# BlueBus.net
KiCad netlist of a schematic drawn in EAGLE
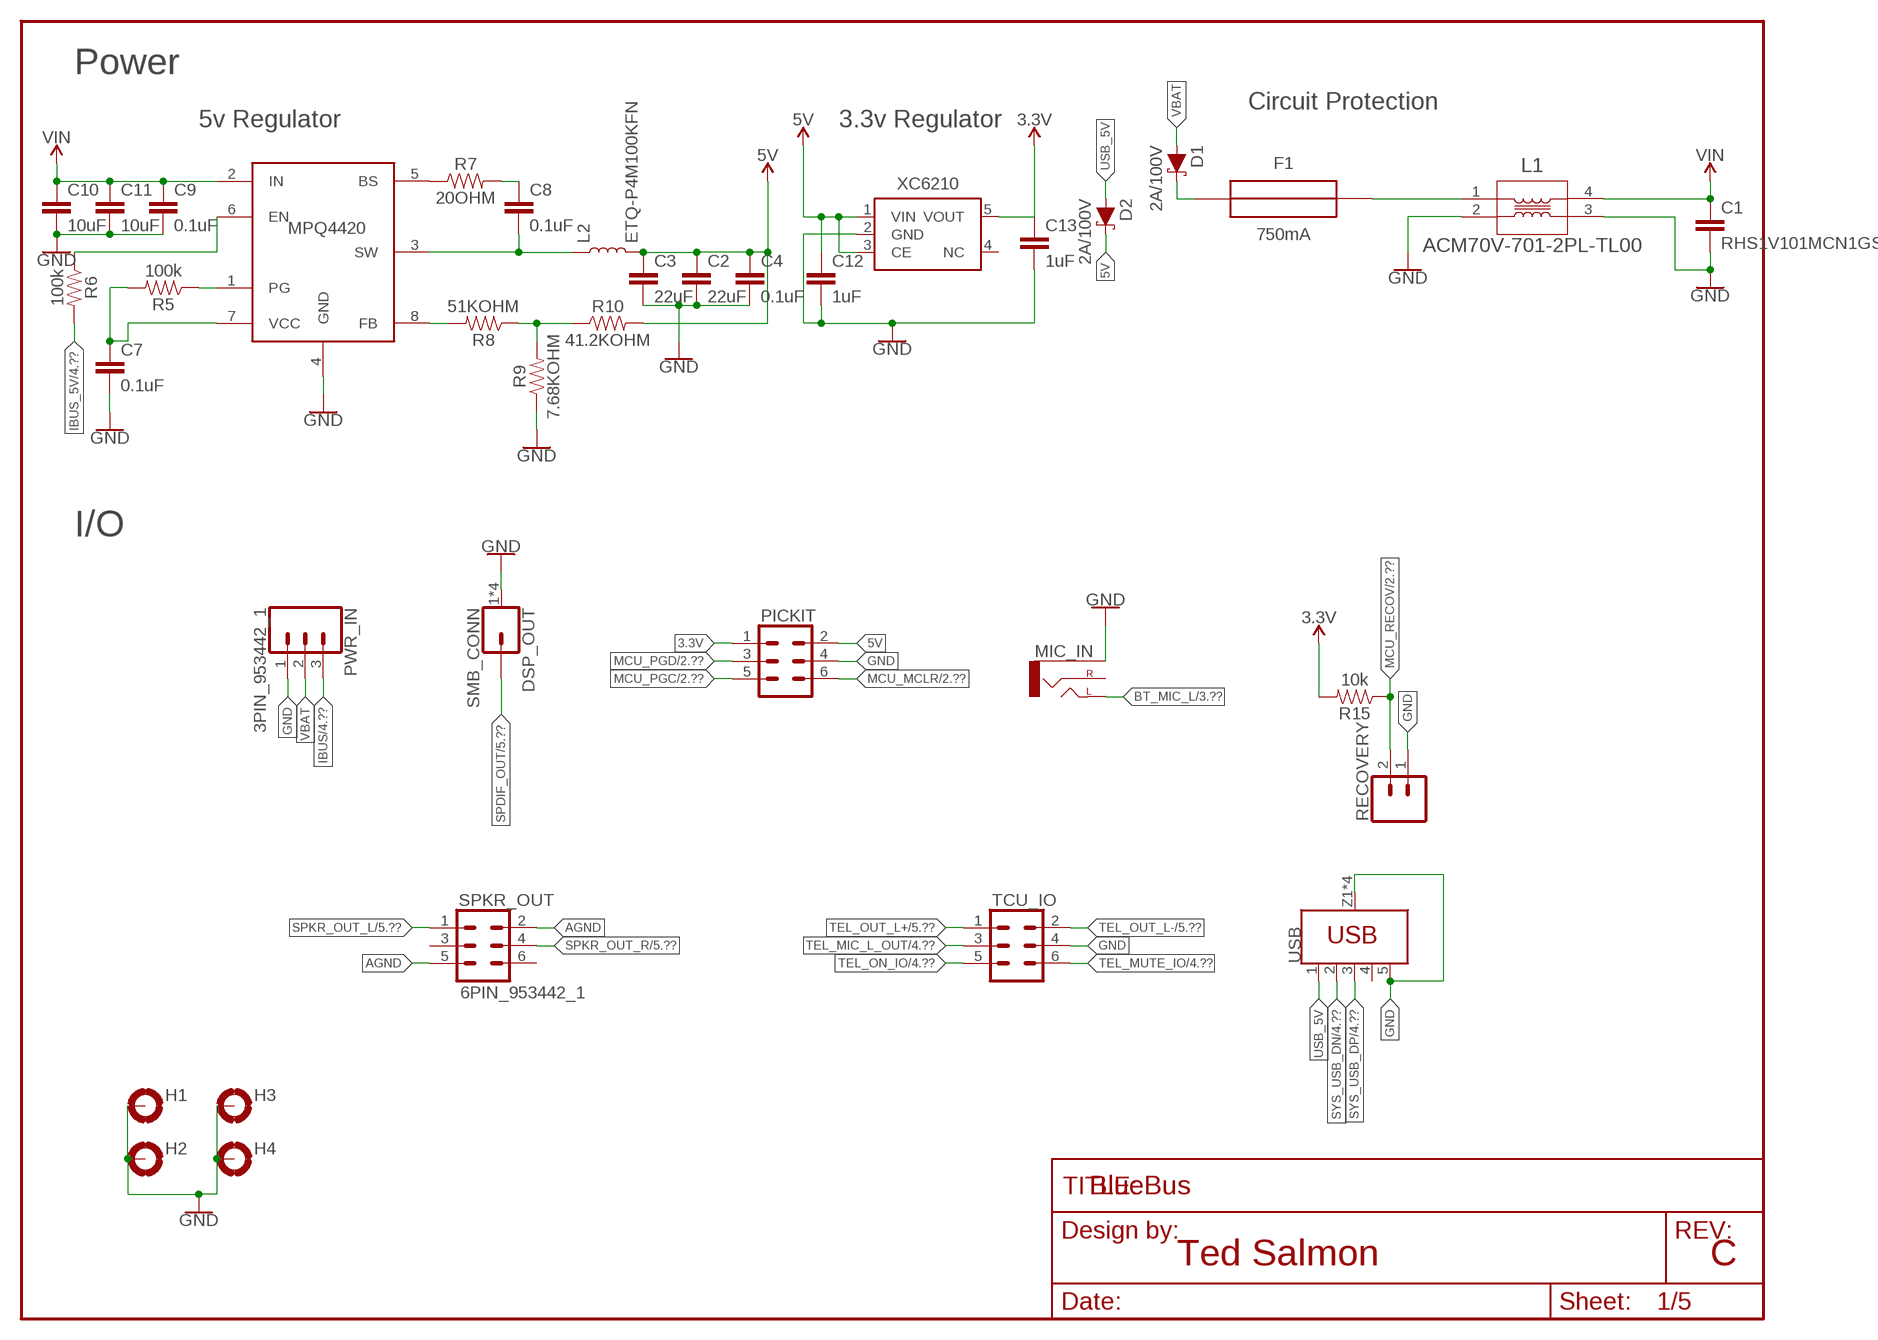
[diagram p0: schematic, sheet 1]
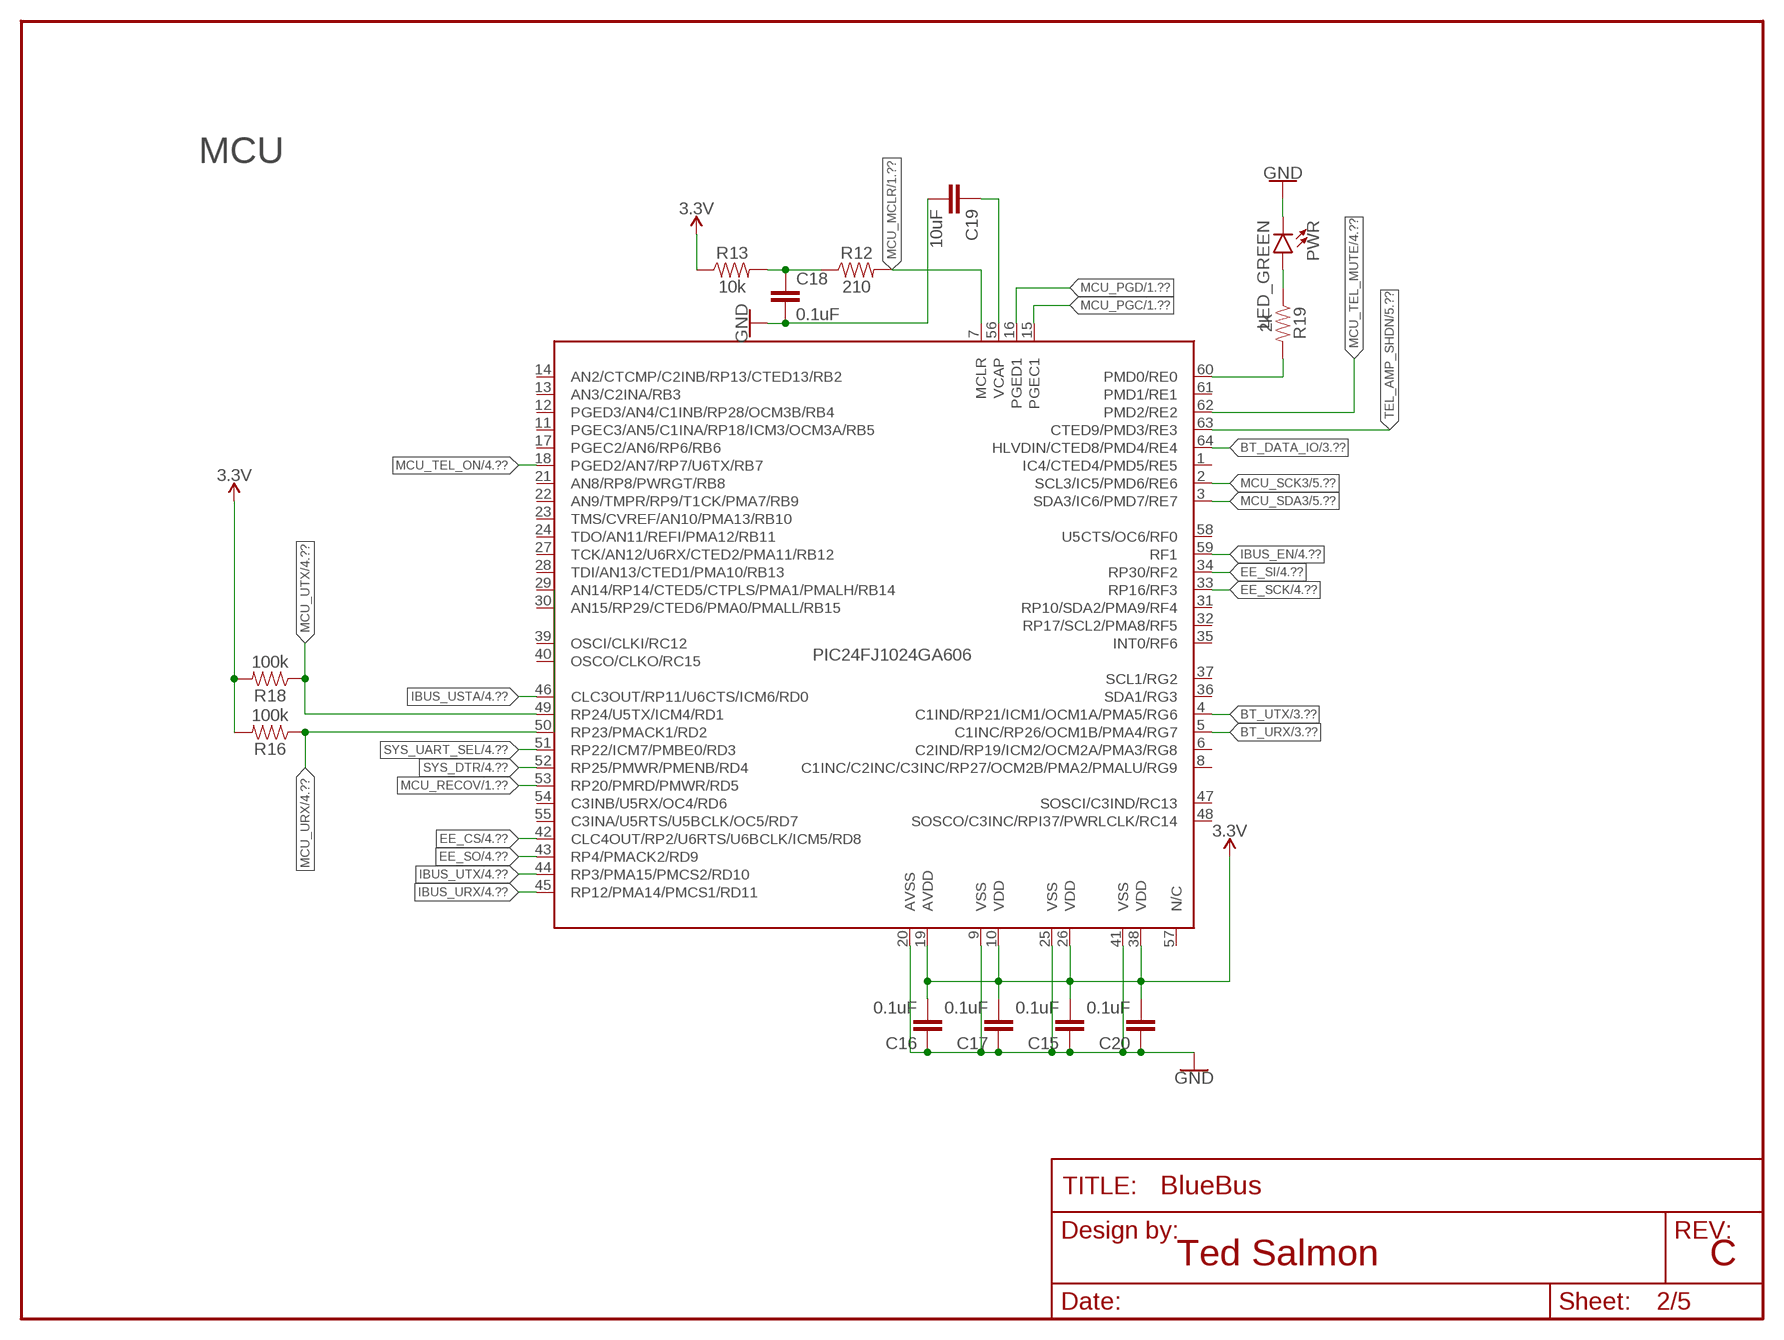
[diagram p1: schematic, sheet 2]
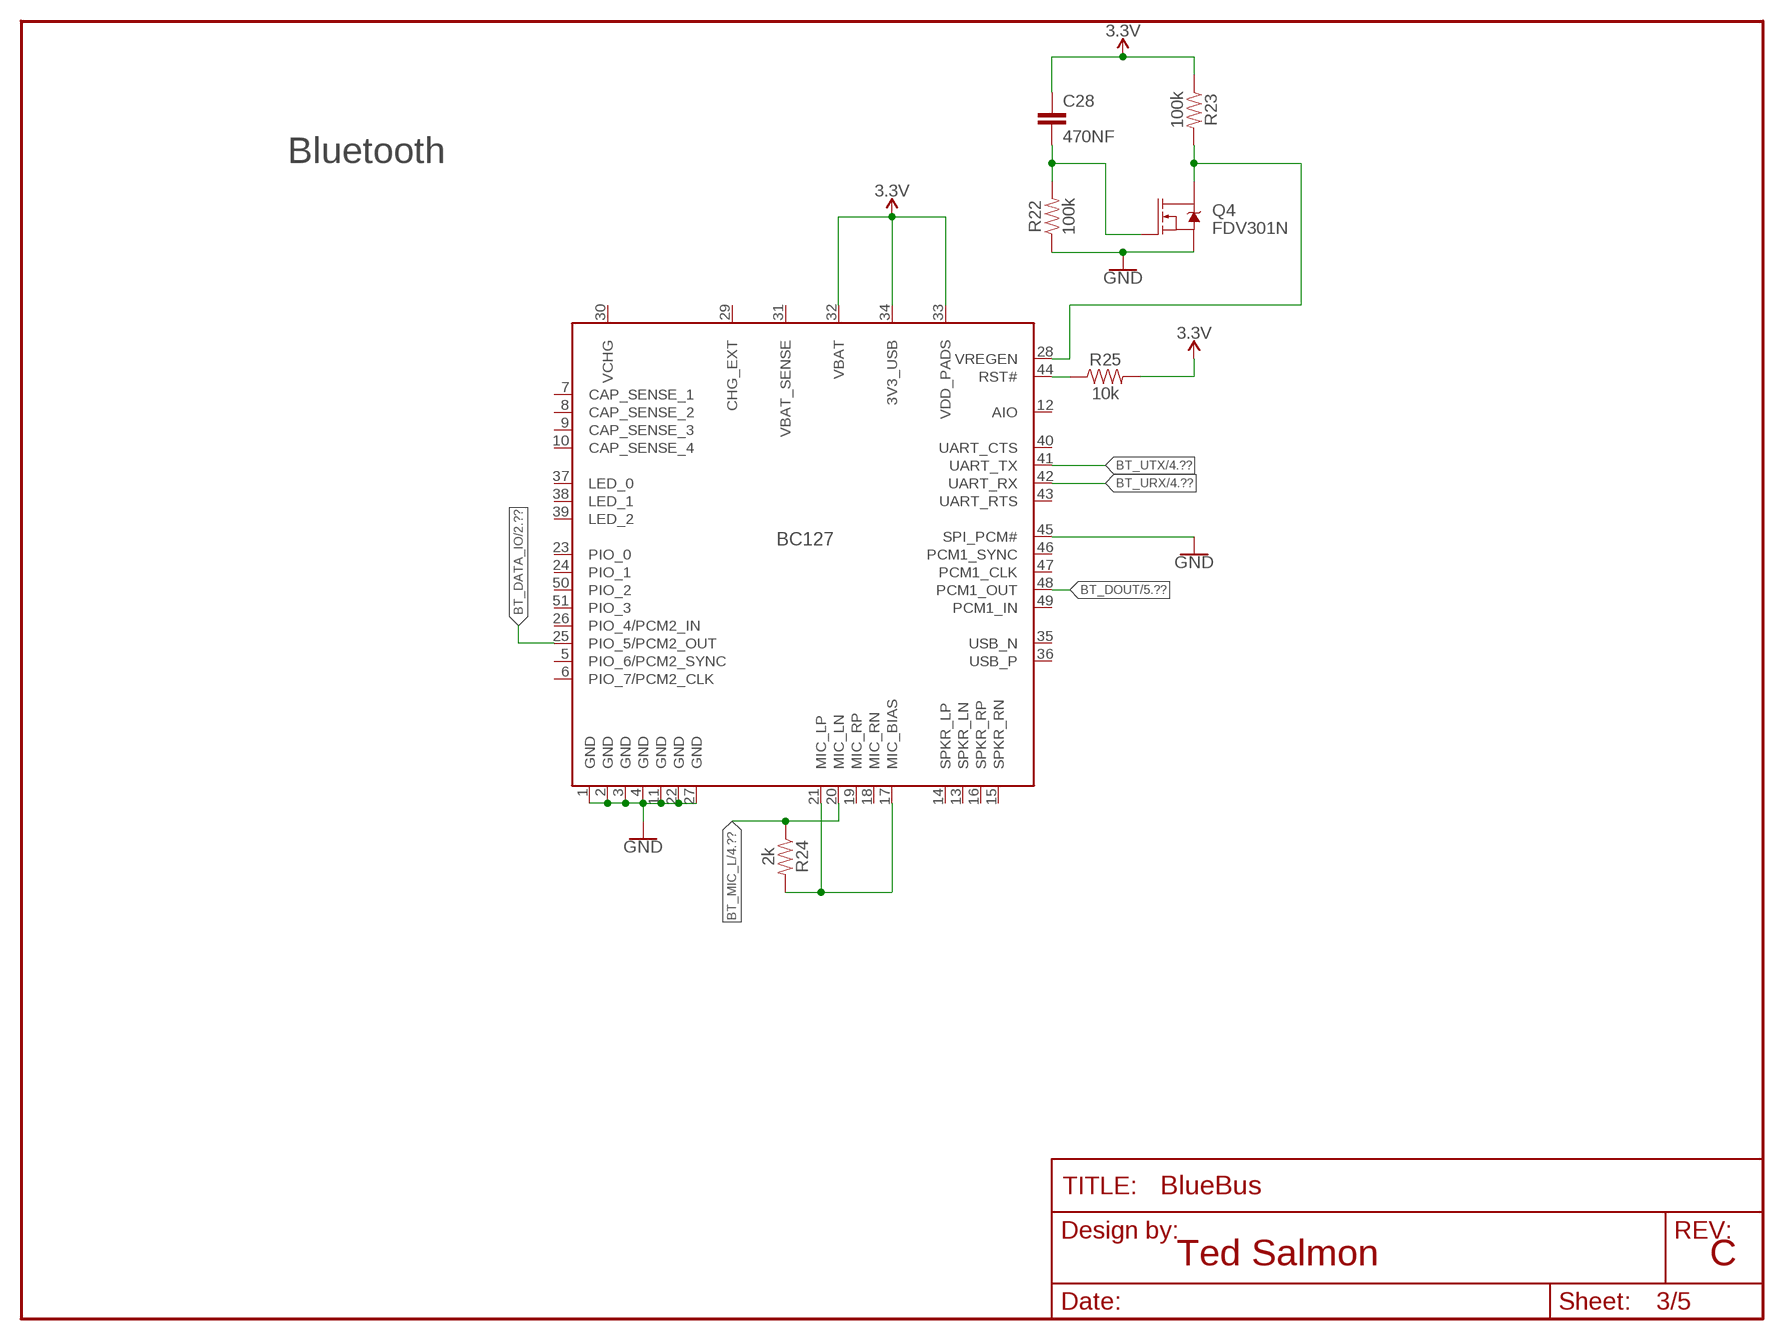
[diagram p2: schematic, sheet 3]
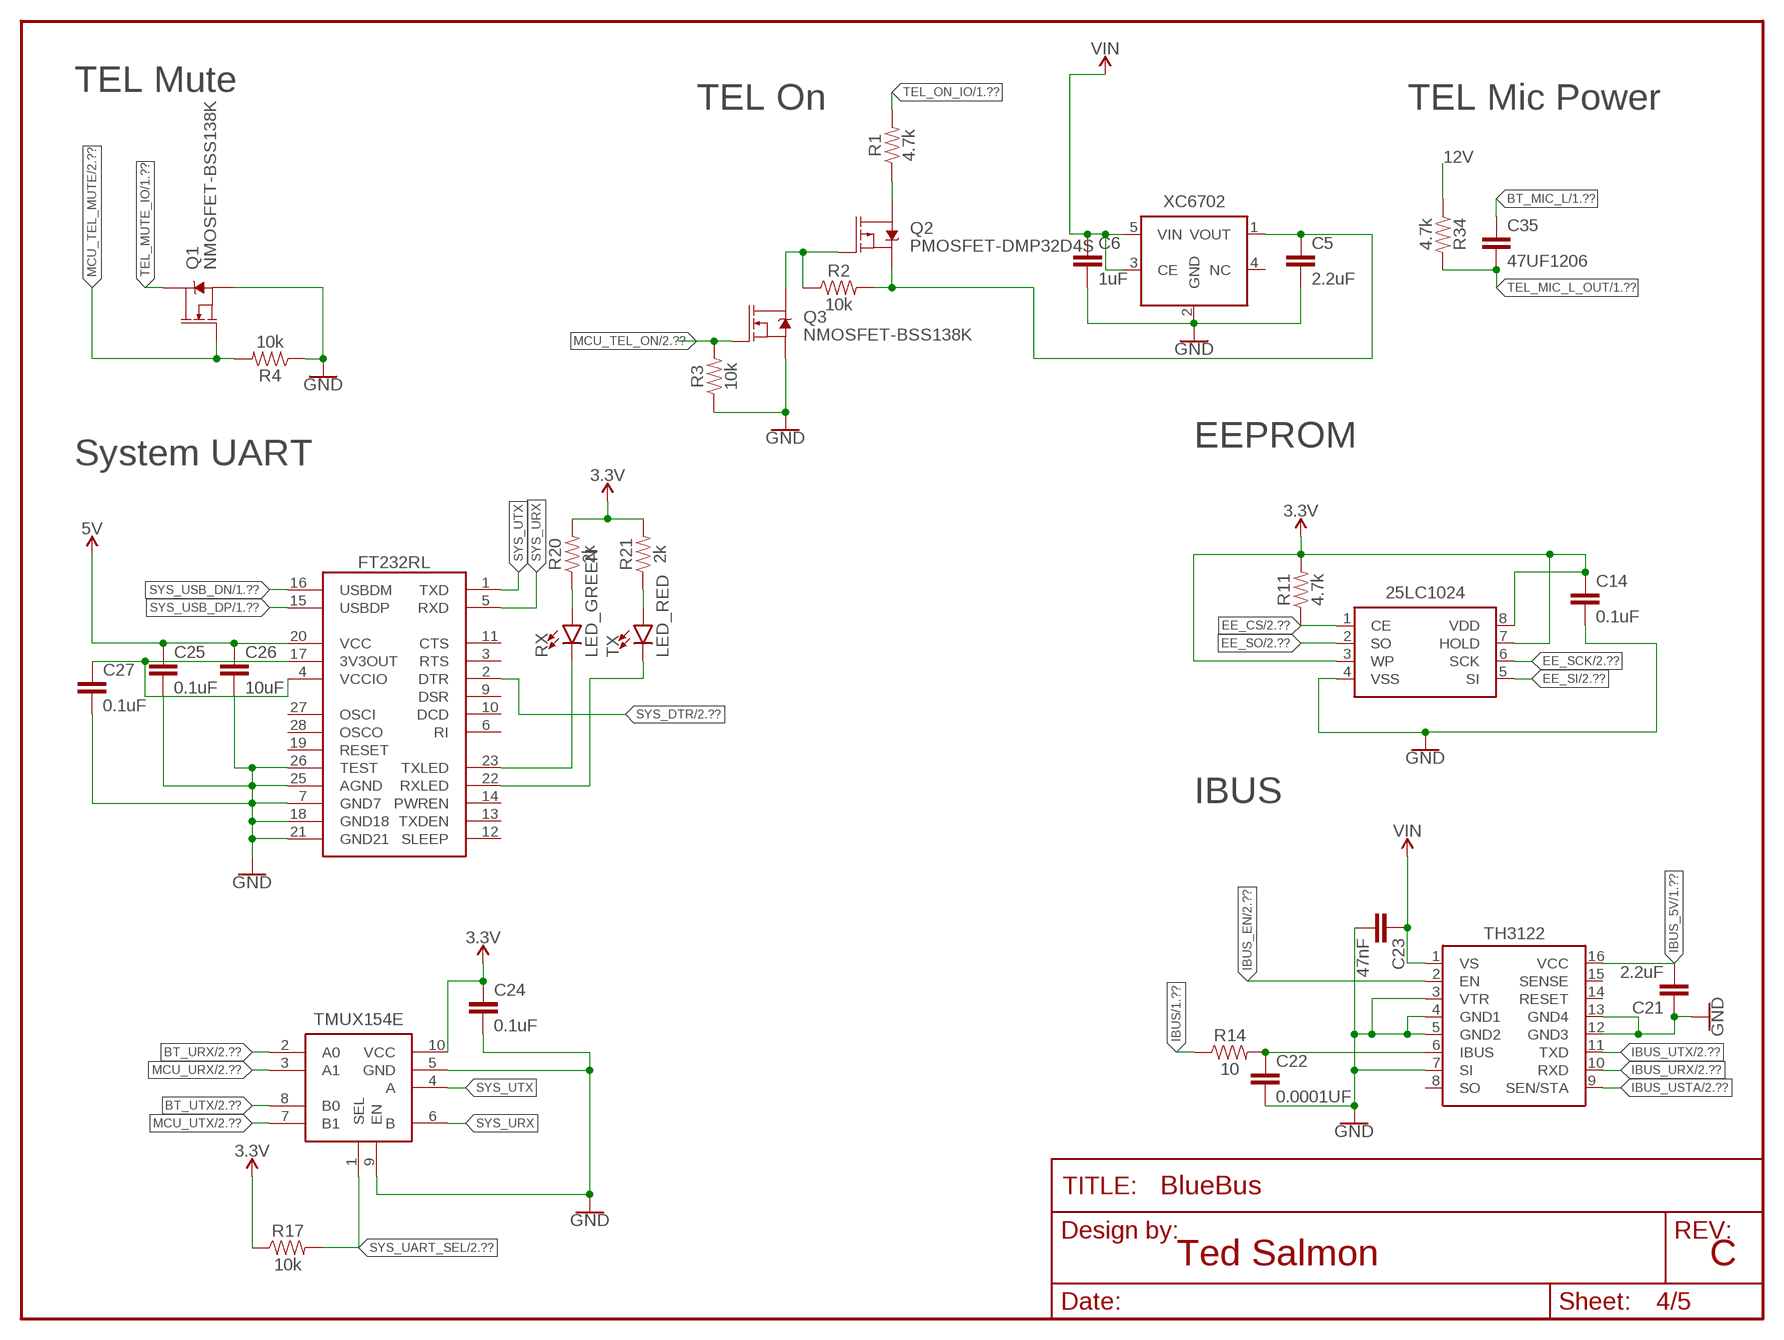
[diagram p3: schematic, sheet 4]
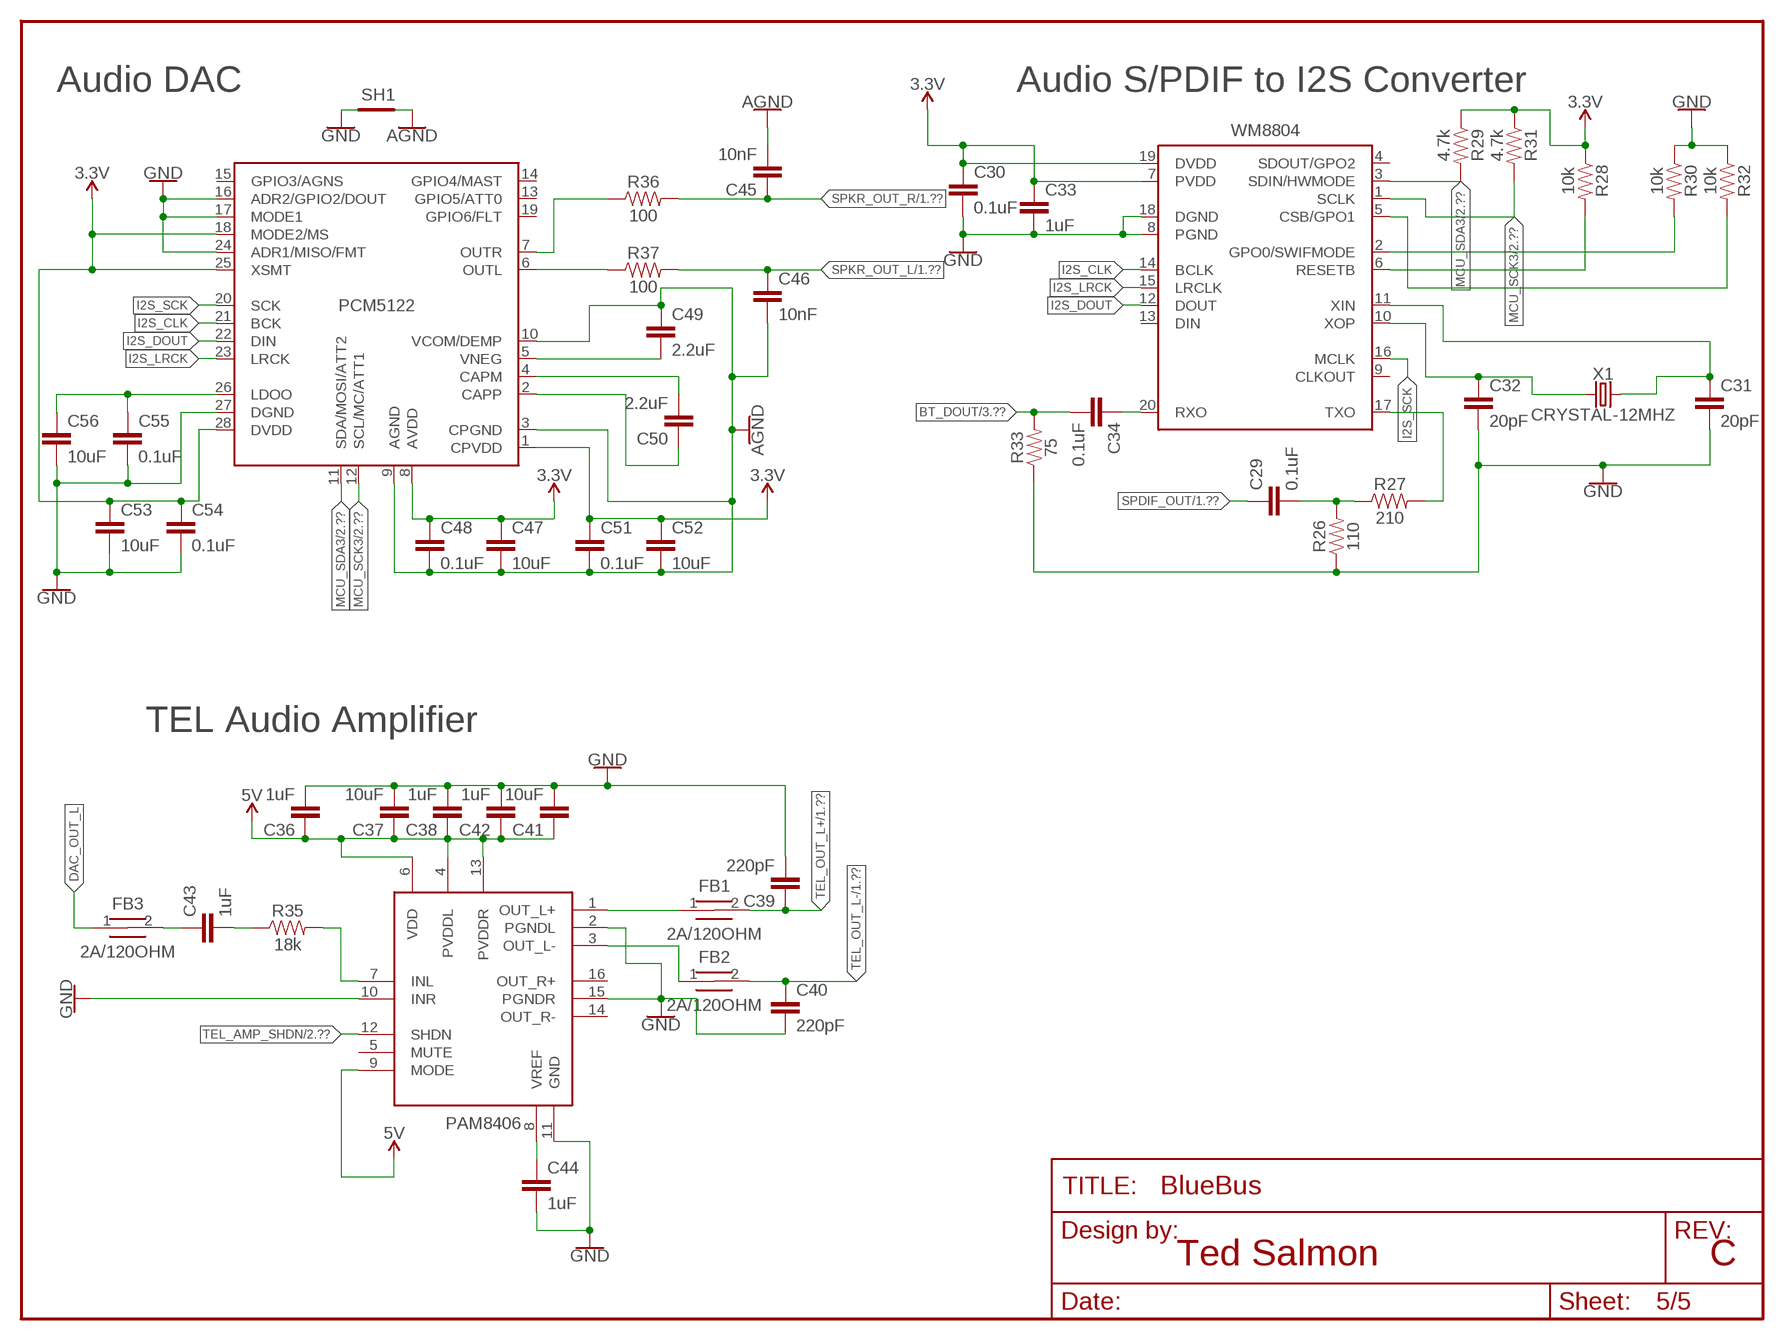
[diagram p4: schematic, sheet 5]

(export (version "E")
  (design (tool "Eeschema 10.0.6"))
  (components
    (comp (ref "C1")
      (value "RHS1V101MCN1GS")
      (footprint "eagle-import:RHS1V101MCN1GS")
      (fields (field (name "MFG") "Nichicon"))
      (libsource (lib "eagle-import") (part "RHS1V101MCN1GS"))
    )
    (comp (ref "C2")
      (value "22uF")
      (footprint "eagle-import:0805")
      (fields (field (name "MFG") "TDK"))
      (libsource (lib "eagle-import") (part "22UF"))
    )
    (comp (ref "C3")
      (value "22uF")
      (footprint "eagle-import:0805")
      (fields (field (name "MFG") "TDK"))
      (libsource (lib "eagle-import") (part "22UF"))
    )
    (comp (ref "C4")
      (value "0.1uF")
      (footprint "eagle-import:0805")
      (fields (field (name "MFG") "KEMET"))
      (libsource (lib "eagle-import") (part "0.1UF"))
    )
    (comp (ref "C7")
      (value "0.1uF")
      (footprint "eagle-import:0805")
      (fields (field (name "MFG") "KEMET"))
      (libsource (lib "eagle-import") (part "0.1UF"))
    )
    (comp (ref "C8")
      (value "0.1uF")
      (footprint "eagle-import:0805")
      (fields (field (name "MFG") "KEMET"))
      (libsource (lib "eagle-import") (part "0.1UF"))
    )
    (comp (ref "C9")
      (value "0.1uF")
      (footprint "eagle-import:0805")
      (fields (field (name "MFG") "KEMET"))
      (libsource (lib "eagle-import") (part "0.1UF"))
    )
    (comp (ref "C10")
      (value "10uF")
      (footprint "eagle-import:1206")
      (fields (field (name "MFG") "TDK"))
      (libsource (lib "eagle-import") (part "10UF"))
    )
    (comp (ref "C11")
      (value "10uF")
      (footprint "eagle-import:1206")
      (fields (field (name "MFG") "TDK"))
      (libsource (lib "eagle-import") (part "10UF"))
    )
    (comp (ref "C12")
      (value "1uF")
      (footprint "eagle-import:0805")
      (fields (field (name "MFG") "TDK"))
      (libsource (lib "eagle-import") (part "1UF"))
    )
    (comp (ref "C13")
      (value "1uF")
      (footprint "eagle-import:0805")
      (fields (field (name "MFG") "TDK"))
      (libsource (lib "eagle-import") (part "1UF"))
    )
    (comp (ref "D1")
      (value "2A/100V")
      (footprint "eagle-import:SOD123")
      (fields (field (name "MFG") "STMicroelectronics"))
      (libsource (lib "eagle-import") (part "SCHOTTKYDIODE2A100V"))
    )
    (comp (ref "D2")
      (value "2A/100V")
      (footprint "eagle-import:SOD123")
      (fields (field (name "MFG") "STMicroelectronics"))
      (libsource (lib "eagle-import") (part "SCHOTTKYDIODE2A100V"))
    )
    (comp (ref "DSP_OUT")
      (value "SMB_CONN")
      (footprint "eagle-import:MOLEX_SMB")
      (libsource (lib "eagle-import") (part "SMB_CONN"))
    )
    (comp (ref "F1")
      (value "750mA")
      (footprint "eagle-import:LITTLEFUSE")
      (fields (field (name "MFG") "LITTLEBLOCK"))
      (libsource (lib "eagle-import") (part "LITTLEBLOCK_FUSE_.75A"))
    )
    (comp (ref "FRAME1")
      (value "FRAME-LETTER")
      (footprint "eagle-import:DUMMY")
      (libsource (lib "eagle-import") (part "FRAME-LETTER"))
    )
    (comp (ref "H1")
      (value "2,0-PAD")
      (footprint "eagle-import:2.0-PAD")
      (libsource (lib "eagle-import") (part "2,0-PAD"))
    )
    (comp (ref "H2")
      (value "2,0-PAD")
      (footprint "eagle-import:2.0-PAD")
      (libsource (lib "eagle-import") (part "2,0-PAD"))
    )
    (comp (ref "H3")
      (value "2,0-PAD")
      (footprint "eagle-import:2.0-PAD")
      (libsource (lib "eagle-import") (part "2,0-PAD"))
    )
    (comp (ref "H4")
      (value "2,0-PAD")
      (footprint "eagle-import:2.0-PAD")
      (libsource (lib "eagle-import") (part "2,0-PAD"))
    )
    (comp (ref "L1")
      (value "ACM70V-701-2PL-TL00")
      (footprint "eagle-import:ACM70V-701-2PL-TL00")
      (fields (field (name "MFG") "TDK"))
      (libsource (lib "eagle-import") (part "ACM70V-701-2PL-TL00"))
    )
    (comp (ref "L2")
      (value "ETQ-P4M100KFN")
      (footprint "eagle-import:PCC-M0648M-LE")
      (fields (field (name "MFG") "PANASONIC"))
      (libsource (lib "eagle-import") (part "ETQ-P4M100KFN"))
    )
    (comp (ref "MIC_IN")
      (value "AUDIO-CUI-SJ-3523-SMT")
      (footprint "eagle-import:AUDIO-CUI-SJ-352X-SMT")
      (libsource (lib "eagle-import") (part "AUDIO-CUI-SJ-3523-SMT"))
    )
    (comp (ref "MPQ4420")
      (value "MPQ4420")
      (footprint "eagle-import:TSOT23-8")
      (libsource (lib "eagle-import") (part "MPQ4420"))
    )
    (comp (ref "PICKIT")
      (value "6PIN_JUMPER")
      (footprint "eagle-import:2X3")
      (libsource (lib "eagle-import") (part "6PIN_JUMPER"))
    )
    (comp (ref "PWR_IN")
      (value "3PIN_953442_1")
      (footprint "eagle-import:TE_MQS_3PIN")
      (libsource (lib "eagle-import") (part "3PIN_953442_1"))
    )
    (comp (ref "R5")
      (value "100k")
      (footprint "eagle-import:0805")
      (libsource (lib "eagle-import") (part "100KOHM"))
    )
    (comp (ref "R6")
      (value "100k")
      (footprint "eagle-import:0805")
      (libsource (lib "eagle-import") (part "100KOHM"))
    )
    (comp (ref "R7")
      (value "20OHM")
      (footprint "eagle-import:0805")
      (libsource (lib "eagle-import") (part "20OHM"))
    )
    (comp (ref "R8")
      (value "51KOHM")
      (footprint "eagle-import:0805")
      (libsource (lib "eagle-import") (part "51KOHM"))
    )
    (comp (ref "R9")
      (value "7.68KOHM")
      (footprint "eagle-import:0805")
      (libsource (lib "eagle-import") (part "7.68KOHM"))
    )
    (comp (ref "R10")
      (value "41.2KOHM")
      (footprint "eagle-import:0805")
      (libsource (lib "eagle-import") (part "41.2KOHM"))
    )
    (comp (ref "R15")
      (value "10k")
      (footprint "eagle-import:0805")
      (fields (field (name "MFG") "Panasonic"))
      (libsource (lib "eagle-import") (part "10KOHM"))
    )
    (comp (ref "RECOVERY")
      (value "2PIN_JUMPER")
      (footprint "eagle-import:1X02")
      (libsource (lib "eagle-import") (part "2PIN_JUMPER"))
    )
    (comp (ref "SPKR_OUT")
      (value "6PIN_953442_1")
      (footprint "eagle-import:TE_MQS_6PIN")
      (libsource (lib "eagle-import") (part "6PIN_953442_1"))
    )
    (comp (ref "TCU_IO")
      (value "6PIN_5_103166_1")
      (footprint "eagle-import:TE_AMPMODU_6_PIN")
      (libsource (lib "eagle-import") (part "6PIN_5_103166_1"))
    )
    (comp (ref "USB")
      (value "USB_WURTH_629105150521")
      (footprint "eagle-import:629105150521")
      (libsource (lib "eagle-import") (part "USB_WURTH_629105150521"))
    )
    (comp (ref "XC6210")
      (value "XC6210SOT25")
      (footprint "eagle-import:SOT23-5")
      (libsource (lib "eagle-import") (part "XC6210SOT25"))
    )
    (comp (ref "25LC1024")
      (value "25LC1024")
      (footprint "eagle-import:SOIJ-8")
      (libsource (lib "eagle-import") (part "25LC1024"))
    )
    (comp (ref "C5")
      (value "2.2uF")
      (footprint "eagle-import:0805")
      (fields (field (name "MFG") "TDK"))
      (libsource (lib "eagle-import") (part "2.2UF"))
    )
    (comp (ref "C6")
      (value "1uF")
      (footprint "eagle-import:0805")
      (fields (field (name "MFG") "TDK"))
      (libsource (lib "eagle-import") (part "1UF"))
    )
    (comp (ref "C14")
      (value "0.1uF")
      (footprint "eagle-import:0805")
      (fields (field (name "MFG") "KEMET"))
      (libsource (lib "eagle-import") (part "0.1UF"))
    )
    (comp (ref "C21")
      (value "2.2uF")
      (footprint "eagle-import:0805")
      (fields (field (name "MFG") "TDK"))
      (libsource (lib "eagle-import") (part "2.2UF"))
    )
    (comp (ref "C22")
      (value "0.0001UF")
      (footprint "eagle-import:0805")
      (libsource (lib "eagle-import") (part "0.0001UF"))
    )
    (comp (ref "C23")
      (value "47nF")
      (footprint "eagle-import:0805")
      (fields (field (name "MFG") "AVX"))
      (libsource (lib "eagle-import") (part "47NF"))
    )
    (comp (ref "C24")
      (value "0.1uF")
      (footprint "eagle-import:0805")
      (fields (field (name "MFG") "KEMET"))
      (libsource (lib "eagle-import") (part "0.1UF"))
    )
    (comp (ref "C25")
      (value "0.1uF")
      (footprint "eagle-import:0805")
      (fields (field (name "MFG") "KEMET"))
      (libsource (lib "eagle-import") (part "0.1UF"))
    )
    (comp (ref "C26")
      (value "10uF")
      (footprint "eagle-import:0805")
      (fields (field (name "MFG") "TDK"))
      (libsource (lib "eagle-import") (part "10UF2012"))
    )
    (comp (ref "C27")
      (value "0.1uF")
      (footprint "eagle-import:0805")
      (fields (field (name "MFG") "KEMET"))
      (libsource (lib "eagle-import") (part "0.1UF"))
    )
    (comp (ref "C35")
      (value "47UF1206")
      (footprint "eagle-import:1206")
      (fields (field (name "MFG") "MURATA"))
      (libsource (lib "eagle-import") (part "47UF1206"))
    )
    (comp (ref "FRAME3")
      (value "FRAME-LETTER")
      (footprint "eagle-import:DUMMY")
      (libsource (lib "eagle-import") (part "FRAME-LETTER"))
    )
    (comp (ref "FT232RL")
      (value "FT232RL")
      (footprint "eagle-import:SSOP28")
      (libsource (lib "eagle-import") (part "FT232RL"))
    )
    (comp (ref "Q1")
      (value "NMOSFET-BSS138K")
      (footprint "eagle-import:SOT-23")
      (libsource (lib "eagle-import") (part "NMOSFET-BSS138K"))
    )
    (comp (ref "Q2")
      (value "PMOSFET-DMP32D4S")
      (footprint "eagle-import:SOT-23")
      (fields (field (name "MFG") "Diodes Inc") (field (name "MPN") "DMP32D4S"))
      (libsource (lib "eagle-import") (part "PMOSFET-DMP32D4S"))
    )
    (comp (ref "Q3")
      (value "NMOSFET-BSS138K")
      (footprint "eagle-import:SOT-23")
      (libsource (lib "eagle-import") (part "NMOSFET-BSS138K"))
    )
    (comp (ref "R1")
      (value "4.7k")
      (footprint "eagle-import:0805")
      (fields (field (name "MFG") "Panasonic"))
      (libsource (lib "eagle-import") (part "4.7KOHM"))
    )
    (comp (ref "R2")
      (value "10k")
      (footprint "eagle-import:0805")
      (fields (field (name "MFG") "Panasonic"))
      (libsource (lib "eagle-import") (part "10KOHM"))
    )
    (comp (ref "R3")
      (value "10k")
      (footprint "eagle-import:0805")
      (fields (field (name "MFG") "Panasonic"))
      (libsource (lib "eagle-import") (part "10KOHM"))
    )
    (comp (ref "R4")
      (value "10k")
      (footprint "eagle-import:0805")
      (fields (field (name "MFG") "Panasonic"))
      (libsource (lib "eagle-import") (part "10KOHM"))
    )
    (comp (ref "R11")
      (value "4.7k")
      (footprint "eagle-import:0805")
      (fields (field (name "MFG") "Panasonic"))
      (libsource (lib "eagle-import") (part "4.7KOHM"))
    )
    (comp (ref "R14")
      (value "10")
      (footprint "eagle-import:0805")
      (fields (field (name "MFG") "Panasonic"))
      (libsource (lib "eagle-import") (part "10OHM"))
    )
    (comp (ref "R17")
      (value "10k")
      (footprint "eagle-import:0805")
      (fields (field (name "MFG") "Panasonic"))
      (libsource (lib "eagle-import") (part "10KOHM"))
    )
    (comp (ref "R20")
      (value "2k")
      (footprint "eagle-import:0805")
      (fields (field (name "MFG") "ROHM"))
      (libsource (lib "eagle-import") (part "2KOHM"))
    )
    (comp (ref "R21")
      (value "2k")
      (footprint "eagle-import:0805")
      (fields (field (name "MFG") "ROHM"))
      (libsource (lib "eagle-import") (part "2KOHM"))
    )
    (comp (ref "R34")
      (value "4.7k")
      (footprint "eagle-import:0805")
      (fields (field (name "MFG") "Panasonic"))
      (libsource (lib "eagle-import") (part "4.7KOHM"))
    )
    (comp (ref "RX")
      (value "LED_GREEN")
      (footprint "eagle-import:LED-0805")
      (libsource (lib "eagle-import") (part "LED_GREEN"))
    )
    (comp (ref "TH3122")
      (value "TH3122.4")
      (footprint "eagle-import:SOIC16DF")
      (libsource (lib "eagle-import") (part "TH3122.4"))
    )
    (comp (ref "TMUX154E")
      (value "TMUX154E")
      (footprint "eagle-import:VSSOP10")
      (libsource (lib "eagle-import") (part "TMUX154E"))
    )
    (comp (ref "TX")
      (value "LED_RED")
      (footprint "eagle-import:LED-0805")
      (libsource (lib "eagle-import") (part "LED_RED"))
    )
    (comp (ref "XC6702")
      (value "XC6702DC018PR-G")
      (footprint "eagle-import:SOT-89-5")
      (libsource (lib "eagle-import") (part "XC6702DC018PR-G"))
    )
    (comp (ref "C15")
      (value "0.1uF")
      (footprint "eagle-import:0805")
      (fields (field (name "MFG") "KEMET"))
      (libsource (lib "eagle-import") (part "0.1UF"))
    )
    (comp (ref "C16")
      (value "0.1uF")
      (footprint "eagle-import:0805")
      (fields (field (name "MFG") "KEMET"))
      (libsource (lib "eagle-import") (part "0.1UF"))
    )
    (comp (ref "C17")
      (value "0.1uF")
      (footprint "eagle-import:0805")
      (fields (field (name "MFG") "KEMET"))
      (libsource (lib "eagle-import") (part "0.1UF"))
    )
    (comp (ref "C18")
      (value "0.1uF")
      (footprint "eagle-import:0805")
      (fields (field (name "MFG") "KEMET"))
      (libsource (lib "eagle-import") (part "0.1UF"))
    )
    (comp (ref "C19")
      (value "10uF")
      (footprint "eagle-import:0805")
      (fields (field (name "MFG") "TDK"))
      (libsource (lib "eagle-import") (part "10UF2012"))
    )
    (comp (ref "C20")
      (value "0.1uF")
      (footprint "eagle-import:0805")
      (fields (field (name "MFG") "KEMET"))
      (libsource (lib "eagle-import") (part "0.1UF"))
    )
    (comp (ref "FRAME2")
      (value "FRAME-LETTER")
      (footprint "eagle-import:DUMMY")
      (libsource (lib "eagle-import") (part "FRAME-LETTER"))
    )
    (comp (ref "PIC24FJ1024GA606")
      (value "PIC24FJ1024GA606")
      (footprint "eagle-import:TQFP64")
      (libsource (lib "eagle-import") (part "PIC24FJ1024GA606"))
    )
    (comp (ref "PWR")
      (value "LED_GREEN")
      (footprint "eagle-import:LED-0805")
      (libsource (lib "eagle-import") (part "LED_GREEN"))
    )
    (comp (ref "R12")
      (value "210")
      (footprint "eagle-import:0805")
      (libsource (lib "eagle-import") (part "210OHM"))
    )
    (comp (ref "R13")
      (value "10k")
      (footprint "eagle-import:0805")
      (fields (field (name "MFG") "Panasonic"))
      (libsource (lib "eagle-import") (part "10KOHM"))
    )
    (comp (ref "R16")
      (value "100k")
      (footprint "eagle-import:0805")
      (libsource (lib "eagle-import") (part "100KOHM"))
    )
    (comp (ref "R18")
      (value "100k")
      (footprint "eagle-import:0805")
      (libsource (lib "eagle-import") (part "100KOHM"))
    )
    (comp (ref "R19")
      (value "2k")
      (footprint "eagle-import:0805")
      (fields (field (name "MFG") "ROHM"))
      (libsource (lib "eagle-import") (part "2KOHM"))
    )
    (comp (ref "BC127")
      (value "BC127")
      (footprint "eagle-import:BC127")
      (libsource (lib "eagle-import") (part "BC127"))
    )
    (comp (ref "C28")
      (value "470NF")
      (footprint "eagle-import:0805")
      (libsource (lib "eagle-import") (part "470NF"))
    )
    (comp (ref "FRAME4")
      (value "FRAME-LETTER")
      (footprint "eagle-import:DUMMY")
      (libsource (lib "eagle-import") (part "FRAME-LETTER"))
    )
    (comp (ref "Q4")
      (value "FDV301N")
      (footprint "eagle-import:SOT-23")
      (libsource (lib "eagle-import") (part "FDV301N"))
    )
    (comp (ref "R22")
      (value "100k")
      (footprint "eagle-import:0805")
      (libsource (lib "eagle-import") (part "100KOHM"))
    )
    (comp (ref "R23")
      (value "100k")
      (footprint "eagle-import:0805")
      (libsource (lib "eagle-import") (part "100KOHM"))
    )
    (comp (ref "R24")
      (value "2k")
      (footprint "eagle-import:0805")
      (fields (field (name "MFG") "ROHM"))
      (libsource (lib "eagle-import") (part "2KOHM"))
    )
    (comp (ref "R25")
      (value "10k")
      (footprint "eagle-import:0805")
      (fields (field (name "MFG") "Panasonic"))
      (libsource (lib "eagle-import") (part "10KOHM"))
    )
    (comp (ref "C29")
      (value "0.1uF")
      (footprint "eagle-import:0805")
      (fields (field (name "MFG") "KEMET"))
      (libsource (lib "eagle-import") (part "0.1UF"))
    )
    (comp (ref "C30")
      (value "0.1uF")
      (footprint "eagle-import:0805")
      (fields (field (name "MFG") "KEMET"))
      (libsource (lib "eagle-import") (part "0.1UF"))
    )
    (comp (ref "C31")
      (value "20pF")
      (footprint "eagle-import:0805")
      (libsource (lib "eagle-import") (part "20PF"))
    )
    (comp (ref "C32")
      (value "20pF")
      (footprint "eagle-import:0805")
      (libsource (lib "eagle-import") (part "20PF"))
    )
    (comp (ref "C33")
      (value "1uF")
      (footprint "eagle-import:0805")
      (fields (field (name "MFG") "TDK"))
      (libsource (lib "eagle-import") (part "1UF"))
    )
    (comp (ref "C34")
      (value "0.1uF")
      (footprint "eagle-import:0805")
      (fields (field (name "MFG") "KEMET"))
      (libsource (lib "eagle-import") (part "0.1UF"))
    )
    (comp (ref "C36")
      (value "1uF")
      (footprint "eagle-import:0805")
      (fields (field (name "MFG") "TDK"))
      (libsource (lib "eagle-import") (part "1UF"))
    )
    (comp (ref "C37")
      (value "10uF")
      (footprint "eagle-import:0805")
      (fields (field (name "MFG") "TDK"))
      (libsource (lib "eagle-import") (part "10UF2012"))
    )
    (comp (ref "C38")
      (value "1uF")
      (footprint "eagle-import:0805")
      (fields (field (name "MFG") "TDK"))
      (libsource (lib "eagle-import") (part "1UF"))
    )
    (comp (ref "C39")
      (value "220pF")
      (footprint "eagle-import:0805")
      (fields (field (name "MFG") "KEMET"))
      (libsource (lib "eagle-import") (part "220PF"))
    )
    (comp (ref "C40")
      (value "220pF")
      (footprint "eagle-import:0805")
      (fields (field (name "MFG") "KEMET"))
      (libsource (lib "eagle-import") (part "220PF"))
    )
    (comp (ref "C41")
      (value "10uF")
      (footprint "eagle-import:0805")
      (fields (field (name "MFG") "TDK"))
      (libsource (lib "eagle-import") (part "10UF2012"))
    )
    (comp (ref "C42")
      (value "1uF")
      (footprint "eagle-import:0805")
      (fields (field (name "MFG") "TDK"))
      (libsource (lib "eagle-import") (part "1UF"))
    )
    (comp (ref "C43")
      (value "1uF")
      (footprint "eagle-import:0805")
      (fields (field (name "MFG") "TDK"))
      (libsource (lib "eagle-import") (part "1UF"))
    )
    (comp (ref "C44")
      (value "1uF")
      (footprint "eagle-import:0805")
      (fields (field (name "MFG") "TDK"))
      (libsource (lib "eagle-import") (part "1UF"))
    )
    (comp (ref "C45")
      (value "10nF")
      (footprint "eagle-import:0805")
      (fields (field (name "MFG") "KEMET"))
      (libsource (lib "eagle-import") (part "10NF"))
    )
    (comp (ref "C46")
      (value "10nF")
      (footprint "eagle-import:0805")
      (fields (field (name "MFG") "KEMET"))
      (libsource (lib "eagle-import") (part "10NF"))
    )
    (comp (ref "C47")
      (value "10uF")
      (footprint "eagle-import:0805")
      (fields (field (name "MFG") "TDK"))
      (libsource (lib "eagle-import") (part "10UF2012"))
    )
    (comp (ref "C48")
      (value "0.1uF")
      (footprint "eagle-import:0805")
      (fields (field (name "MFG") "KEMET"))
      (libsource (lib "eagle-import") (part "0.1UF"))
    )
    (comp (ref "C49")
      (value "2.2uF")
      (footprint "eagle-import:0805")
      (fields (field (name "MFG") "TDK"))
      (libsource (lib "eagle-import") (part "2.2UF"))
    )
    (comp (ref "C50")
      (value "2.2uF")
      (footprint "eagle-import:0805")
      (fields (field (name "MFG") "TDK"))
      (libsource (lib "eagle-import") (part "2.2UF"))
    )
    (comp (ref "C51")
      (value "0.1uF")
      (footprint "eagle-import:0805")
      (fields (field (name "MFG") "KEMET"))
      (libsource (lib "eagle-import") (part "0.1UF"))
    )
    (comp (ref "C52")
      (value "10uF")
      (footprint "eagle-import:0805")
      (fields (field (name "MFG") "TDK"))
      (libsource (lib "eagle-import") (part "10UF2012"))
    )
    (comp (ref "C53")
      (value "10uF")
      (footprint "eagle-import:0805")
      (fields (field (name "MFG") "TDK"))
      (libsource (lib "eagle-import") (part "10UF2012"))
    )
    (comp (ref "C54")
      (value "0.1uF")
      (footprint "eagle-import:0805")
      (fields (field (name "MFG") "KEMET"))
      (libsource (lib "eagle-import") (part "0.1UF"))
    )
    (comp (ref "C55")
      (value "0.1uF")
      (footprint "eagle-import:0805")
      (fields (field (name "MFG") "KEMET"))
      (libsource (lib "eagle-import") (part "0.1UF"))
    )
    (comp (ref "C56")
      (value "10uF")
      (footprint "eagle-import:0805")
      (fields (field (name "MFG") "TDK"))
      (libsource (lib "eagle-import") (part "10UF2012"))
    )
    (comp (ref "FB1")
      (value "2A/120OHM")
      (footprint "eagle-import:0805")
      (fields (field (name "MFG") "BOURNS"))
      (libsource (lib "eagle-import") (part "FERRITE_2A/120OHM"))
    )
    (comp (ref "FB2")
      (value "2A/120OHM")
      (footprint "eagle-import:0805")
      (fields (field (name "MFG") "BOURNS"))
      (libsource (lib "eagle-import") (part "FERRITE_2A/120OHM"))
    )
    (comp (ref "FB3")
      (value "2A/120OHM")
      (footprint "eagle-import:0805")
      (fields (field (name "MFG") "BOURNS"))
      (libsource (lib "eagle-import") (part "FERRITE_2A/120OHM"))
    )
    (comp (ref "FRAME5")
      (value "FRAME-LETTER")
      (footprint "eagle-import:DUMMY")
      (libsource (lib "eagle-import") (part "FRAME-LETTER"))
    )
    (comp (ref "PAM8406")
      (value "PAM8406")
      (footprint "eagle-import:SOP-16")
      (libsource (lib "eagle-import") (part "PAM8406"))
    )
    (comp (ref "PCM5122")
      (value "PCM5122")
      (footprint "eagle-import:TSSOP28")
      (libsource (lib "eagle-import") (part "PCM5122"))
    )
    (comp (ref "R26")
      (value "110")
      (footprint "eagle-import:0805")
      (libsource (lib "eagle-import") (part "110OHM"))
    )
    (comp (ref "R27")
      (value "210")
      (footprint "eagle-import:0805")
      (libsource (lib "eagle-import") (part "210OHM"))
    )
    (comp (ref "R28")
      (value "10k")
      (footprint "eagle-import:0805")
      (fields (field (name "MFG") "Panasonic"))
      (libsource (lib "eagle-import") (part "10KOHM"))
    )
    (comp (ref "R29")
      (value "4.7k")
      (footprint "eagle-import:0805")
      (fields (field (name "MFG") "Panasonic"))
      (libsource (lib "eagle-import") (part "4.7KOHM"))
    )
    (comp (ref "R30")
      (value "10k")
      (footprint "eagle-import:0805")
      (fields (field (name "MFG") "Panasonic"))
      (libsource (lib "eagle-import") (part "10KOHM"))
    )
    (comp (ref "R31")
      (value "4.7k")
      (footprint "eagle-import:0805")
      (fields (field (name "MFG") "Panasonic"))
      (libsource (lib "eagle-import") (part "4.7KOHM"))
    )
    (comp (ref "R32")
      (value "10k")
      (footprint "eagle-import:0805")
      (fields (field (name "MFG") "Panasonic"))
      (libsource (lib "eagle-import") (part "10KOHM"))
    )
    (comp (ref "R33")
      (value "75")
      (footprint "eagle-import:0805")
      (fields (field (name "MFG") "Panasonic"))
      (libsource (lib "eagle-import") (part "75OHM"))
    )
    (comp (ref "R35")
      (value "18k")
      (footprint "eagle-import:0805")
      (fields (field (name "MFG") "Panasonic"))
      (libsource (lib "eagle-import") (part "18KOHM"))
    )
    (comp (ref "R36")
      (value "100")
      (footprint "eagle-import:0805")
      (fields (field (name "MFG") "PANASONIC"))
      (libsource (lib "eagle-import") (part "100OHM"))
    )
    (comp (ref "R37")
      (value "100")
      (footprint "eagle-import:0805")
      (fields (field (name "MFG") "PANASONIC"))
      (libsource (lib "eagle-import") (part "100OHM"))
    )
    (comp (ref "SH1")
      (value "SHORTT5")
      (footprint "eagle-import:SHORT_TOP-50")
      (libsource (lib "eagle-import") (part "SHORTT5"))
    )
    (comp (ref "WM8804")
      (value "WM8804")
      (footprint "eagle-import:SSOP20")
      (libsource (lib "eagle-import") (part "WM8804"))
    )
    (comp (ref "X1")
      (value "CRYSTAL-12MHZ")
      (footprint "eagle-import:HC49")
      (libsource (lib "eagle-import") (part "CRYSTAL-12MHZ"))
    )
  )
  (nets
    (net (code "1") (name "3.3V") (class "Default")
      (node (ref "25LC1024") (pin "3") (pinfunction "WP_3") (pintype "bidirectional"))
      (node (ref "25LC1024") (pin "7") (pinfunction "HOLD_7") (pintype "bidirectional"))
      (node (ref "25LC1024") (pin "8") (pinfunction "VDD_8") (pintype "power_in"))
      (node (ref "BC127") (pin "32") (pinfunction "VBAT_32") (pintype "bidirectional"))
      (node (ref "BC127") (pin "33") (pinfunction "VDD_PADS_33") (pintype "power_in"))
      (node (ref "BC127") (pin "34") (pinfunction "3V3_USB_34") (pintype "power_in"))
      (node (ref "C13") (pin "1") (pinfunction "1_1") (pintype "passive"))
      (node (ref "C14") (pin "1") (pinfunction "1_1") (pintype "passive"))
      (node (ref "C15") (pin "2") (pinfunction "2_2") (pintype "passive"))
      (node (ref "C16") (pin "2") (pinfunction "2_2") (pintype "passive"))
      (node (ref "C17") (pin "2") (pinfunction "2_2") (pintype "passive"))
      (node (ref "C20") (pin "2") (pinfunction "2_2") (pintype "passive"))
      (node (ref "C24") (pin "1") (pinfunction "1_1") (pintype "passive"))
      (node (ref "C28") (pin "1") (pinfunction "1_1") (pintype "passive"))
      (node (ref "C30") (pin "1") (pinfunction "1_1") (pintype "passive"))
      (node (ref "C33") (pin "1") (pinfunction "1_1") (pintype "passive"))
      (node (ref "C47") (pin "1") (pinfunction "1_1") (pintype "passive"))
      (node (ref "C48") (pin "1") (pinfunction "1_1") (pintype "passive"))
      (node (ref "C51") (pin "1") (pinfunction "1_1") (pintype "passive"))
      (node (ref "C52") (pin "1") (pinfunction "1_1") (pintype "passive"))
      (node (ref "C53") (pin "1") (pinfunction "1_1") (pintype "passive"))
      (node (ref "C54") (pin "1") (pinfunction "1_1") (pintype "passive"))
      (node (ref "PCM5122") (pin "1") (pinfunction "CPVDD_1") (pintype "power_in"))
      (node (ref "PCM5122") (pin "18") (pinfunction "MODE2/MS_18") (pintype "bidirectional"))
      (node (ref "PCM5122") (pin "25") (pinfunction "XSMT_25") (pintype "input"))
      (node (ref "PCM5122") (pin "28") (pinfunction "DVDD_28") (pintype "power_in"))
      (node (ref "PCM5122") (pin "8") (pinfunction "AVDD_8") (pintype "power_in"))
      (node (ref "PIC24FJ1024GA606") (pin "10") (pinfunction "VDD_10") (pintype "power_in"))
      (node (ref "PIC24FJ1024GA606") (pin "19") (pinfunction "AVDD_19") (pintype "power_in"))
      (node (ref "PIC24FJ1024GA606") (pin "26") (pinfunction "VDD_26") (pintype "power_in"))
      (node (ref "PIC24FJ1024GA606") (pin "38") (pinfunction "VDD_38") (pintype "power_in"))
      (node (ref "PICKIT") (pin "1") (pinfunction "1_1") (pintype "bidirectional"))
      (node (ref "R11") (pin "2") (pinfunction "2_2") (pintype "passive"))
      (node (ref "R13") (pin "1") (pinfunction "1_1") (pintype "passive"))
      (node (ref "R15") (pin "2") (pinfunction "2_2") (pintype "passive"))
      (node (ref "R16") (pin "2") (pinfunction "2_2") (pintype "passive"))
      (node (ref "R17") (pin "1") (pinfunction "1_1") (pintype "passive"))
      (node (ref "R18") (pin "2") (pinfunction "2_2") (pintype "passive"))
      (node (ref "R20") (pin "2") (pinfunction "2_2") (pintype "passive"))
      (node (ref "R21") (pin "2") (pinfunction "2_2") (pintype "passive"))
      (node (ref "R23") (pin "1") (pinfunction "1_1") (pintype "passive"))
      (node (ref "R25") (pin "2") (pinfunction "2_2") (pintype "passive"))
      (node (ref "R28") (pin "1") (pinfunction "1_1") (pintype "passive"))
      (node (ref "R29") (pin "1") (pinfunction "1_1") (pintype "passive"))
      (node (ref "R31") (pin "1") (pinfunction "1_1") (pintype "passive"))
      (node (ref "TMUX154E") (pin "10") (pinfunction "VCC_10") (pintype "power_in"))
      (node (ref "WM8804") (pin "19") (pinfunction "DVDD_19") (pintype "power_in"))
      (node (ref "WM8804") (pin "7") (pinfunction "PVDD_7") (pintype "power_in"))
      (node (ref "XC6210") (pin "5") (pinfunction "VOUT_5") (pintype "power_in"))
    )
    (net (code "2") (name "5V") (class "Default")
      (node (ref "C12") (pin "1") (pinfunction "1_1") (pintype "passive"))
      (node (ref "C2") (pin "1") (pinfunction "1_1") (pintype "passive"))
      (node (ref "C25") (pin "1") (pinfunction "1_1") (pintype "passive"))
      (node (ref "C26") (pin "1") (pinfunction "1_1") (pintype "passive"))
      (node (ref "C3") (pin "1") (pinfunction "1_1") (pintype "passive"))
      (node (ref "C36") (pin "1") (pinfunction "1_1") (pintype "passive"))
      (node (ref "C37") (pin "1") (pinfunction "1_1") (pintype "passive"))
      (node (ref "C38") (pin "1") (pinfunction "1_1") (pintype "passive"))
      (node (ref "C4") (pin "1") (pinfunction "1_1") (pintype "passive"))
      (node (ref "C41") (pin "1") (pinfunction "1_1") (pintype "passive"))
      (node (ref "C42") (pin "1") (pinfunction "1_1") (pintype "passive"))
      (node (ref "D2") (pin "C") (pinfunction "C_C") (pintype "passive"))
      (node (ref "FT232RL") (pin "20") (pinfunction "VCC_20") (pintype "power_in"))
      (node (ref "L2") (pin "2") (pinfunction "2_2") (pintype "passive"))
      (node (ref "PAM8406") (pin "13") (pinfunction "PVDDR_13") (pintype "bidirectional"))
      (node (ref "PAM8406") (pin "4") (pinfunction "PVDDL_4") (pintype "bidirectional"))
      (node (ref "PAM8406") (pin "6") (pinfunction "VDD_6") (pintype "bidirectional"))
      (node (ref "PAM8406") (pin "9") (pinfunction "MODE_9") (pintype "input"))
      (node (ref "PICKIT") (pin "2") (pinfunction "2_2") (pintype "bidirectional"))
      (node (ref "R10") (pin "2") (pinfunction "2_2") (pintype "passive"))
      (node (ref "XC6210") (pin "1") (pinfunction "VIN_1") (pintype "power_in"))
      (node (ref "XC6210") (pin "3") (pinfunction "CE_3") (pintype "power_in"))
    )
    (net (code "3") (name "12V") (class "Default")
      (node (ref "C5") (pin "1") (pinfunction "1_1") (pintype "passive"))
      (node (ref "Q2") (pin "2") (pinfunction "S_2") (pintype "bidirectional"))
      (node (ref "R2") (pin "2") (pinfunction "2_2") (pintype "passive"))
      (node (ref "R34") (pin "1") (pinfunction "1_1") (pintype "passive"))
      (node (ref "XC6702") (pin "1") (pinfunction "VOUT_1") (pintype "power_in"))
    )
    (net (code "4") (name "AGND") (class "Default")
      (node (ref "C45") (pin "2") (pinfunction "2_2") (pintype "passive"))
      (node (ref "C46") (pin "2") (pinfunction "2_2") (pintype "passive"))
      (node (ref "C47") (pin "2") (pinfunction "2_2") (pintype "passive"))
      (node (ref "C48") (pin "2") (pinfunction "2_2") (pintype "passive"))
      (node (ref "C49") (pin "1") (pinfunction "1_1") (pintype "passive"))
      (node (ref "C51") (pin "2") (pinfunction "2_2") (pintype "passive"))
      (node (ref "C52") (pin "2") (pinfunction "2_2") (pintype "passive"))
      (node (ref "PCM5122") (pin "10") (pinfunction "VCOM/DEMP_10") (pintype "input"))
      (node (ref "PCM5122") (pin "3") (pinfunction "CPGND_3") (pintype "bidirectional"))
      (node (ref "PCM5122") (pin "9") (pinfunction "AGND_9") (pintype "bidirectional"))
      (node (ref "SH1") (pin "2") (pinfunction "P$2_2") (pintype "bidirectional"))
      (node (ref "SPKR_OUT") (pin "2") (pinfunction "2_2") (pintype "bidirectional"))
      (node (ref "SPKR_OUT") (pin "5") (pinfunction "5_5") (pintype "bidirectional"))
    )
    (net (code "5") (name "BT_DATA_IO") (class "Default")
      (node (ref "BC127") (pin "25") (pinfunction "PIO_5/PCM2_OUT_25") (pintype "bidirectional"))
      (node (ref "PIC24FJ1024GA606") (pin "64") (pinfunction "HLVDIN/CTED8/PMD4/RE4_64") (pintype "bidirectional"))
    )
    (net (code "6") (name "BT_DOUT") (class "Default")
      (node (ref "BC127") (pin "48") (pinfunction "PCM1_OUT_48") (pintype "bidirectional"))
      (node (ref "C34") (pin "2") (pinfunction "2_2") (pintype "passive"))
      (node (ref "R33") (pin "2") (pinfunction "2_2") (pintype "passive"))
    )
    (net (code "7") (name "BT_MIC_L") (class "Default")
      (node (ref "BC127") (pin "20") (pinfunction "MIC_LN_20") (pintype "input"))
      (node (ref "C35") (pin "1") (pinfunction "1_1") (pintype "passive"))
      (node (ref "MIC_IN") (pin "TIP") (pinfunction "LEFT_TIP") (pintype "bidirectional"))
      (node (ref "R24") (pin "1") (pinfunction "1_1") (pintype "passive"))
    )
    (net (code "8") (name "BT_URX") (class "Default")
      (node (ref "BC127") (pin "42") (pinfunction "UART_RX_42") (pintype "input"))
      (node (ref "PIC24FJ1024GA606") (pin "5") (pinfunction "C1INC/RP26/OCM1B/PMA4/RG7_5") (pintype "bidirectional"))
      (node (ref "TMUX154E") (pin "2") (pinfunction "A0_2") (pintype "bidirectional"))
    )
    (net (code "9") (name "BT_UTX") (class "Default")
      (node (ref "BC127") (pin "41") (pinfunction "UART_TX_41") (pintype "output"))
      (node (ref "PIC24FJ1024GA606") (pin "4") (pinfunction "C1IND/RP21/ICM1/OCM1A/PMA5/RG6_4") (pintype "bidirectional"))
      (node (ref "TMUX154E") (pin "8") (pinfunction "B0_8") (pintype "bidirectional"))
    )
    (net (code "10") (name "CHG_EXT") (class "Default")
      (node (ref "BC127") (pin "29") (pinfunction "CHG_EXT_29") (pintype "power_in"))
    )
    (net (code "11") (name "DAC_OUT_L") (class "Default")
      (node (ref "FB3") (pin "1") (pinfunction "1_1") (pintype "bidirectional"))
      (node (ref "PCM5122") (pin "6") (pinfunction "OUTL_6") (pintype "output"))
      (node (ref "R37") (pin "1") (pinfunction "1_1") (pintype "passive"))
    )
    (net (code "12") (name "EE_CS") (class "Default")
      (node (ref "25LC1024") (pin "1") (pinfunction "CE_1") (pintype "bidirectional"))
      (node (ref "PIC24FJ1024GA606") (pin "42") (pinfunction "CLC4OUT/RP2/U6RTS/U6BCLK/ICM5/RD8_42") (pintype "bidirectional"))
      (node (ref "R11") (pin "1") (pinfunction "1_1") (pintype "passive"))
    )
    (net (code "13") (name "EE_SCK") (class "Default")
      (node (ref "25LC1024") (pin "6") (pinfunction "SCK_6") (pintype "bidirectional"))
      (node (ref "PIC24FJ1024GA606") (pin "33") (pinfunction "RP16/RF3_33") (pintype "bidirectional"))
    )
    (net (code "14") (name "EE_SI") (class "Default")
      (node (ref "25LC1024") (pin "5") (pinfunction "SI_5") (pintype "bidirectional"))
      (node (ref "PIC24FJ1024GA606") (pin "34") (pinfunction "RP30/RF2_34") (pintype "bidirectional"))
    )
    (net (code "15") (name "EE_SO") (class "Default")
      (node (ref "25LC1024") (pin "2") (pinfunction "SO_2") (pintype "bidirectional"))
      (node (ref "PIC24FJ1024GA606") (pin "43") (pinfunction "RP4/PMACK2/RD9_43") (pintype "bidirectional"))
    )
    (net (code "16") (name "GND") (class "Default")
      (node (ref "25LC1024") (pin "4") (pinfunction "VSS_4") (pintype "power_in"))
      (node (ref "BC127") (pin "1") (pinfunction "GND_1") (pintype "bidirectional"))
      (node (ref "BC127") (pin "11") (pinfunction "GND_11") (pintype "bidirectional"))
      (node (ref "BC127") (pin "2") (pinfunction "GND_2") (pintype "bidirectional"))
      (node (ref "BC127") (pin "22") (pinfunction "GND_22") (pintype "bidirectional"))
      (node (ref "BC127") (pin "27") (pinfunction "GND_27") (pintype "bidirectional"))
      (node (ref "BC127") (pin "3") (pinfunction "GND_3") (pintype "bidirectional"))
      (node (ref "BC127") (pin "4") (pinfunction "GND_4") (pintype "bidirectional"))
      (node (ref "BC127") (pin "45") (pinfunction "SPI_PCM#_45") (pintype "input"))
      (node (ref "C1") (pin "2") (pinfunction "2_2") (pintype "passive"))
      (node (ref "C10") (pin "2") (pinfunction "2_2") (pintype "passive"))
      (node (ref "C11") (pin "2") (pinfunction "2_2") (pintype "passive"))
      (node (ref "C12") (pin "2") (pinfunction "2_2") (pintype "passive"))
      (node (ref "C13") (pin "2") (pinfunction "2_2") (pintype "passive"))
      (node (ref "C14") (pin "2") (pinfunction "2_2") (pintype "passive"))
      (node (ref "C15") (pin "1") (pinfunction "1_1") (pintype "passive"))
      (node (ref "C16") (pin "1") (pinfunction "1_1") (pintype "passive"))
      (node (ref "C17") (pin "1") (pinfunction "1_1") (pintype "passive"))
      (node (ref "C18") (pin "2") (pinfunction "2_2") (pintype "passive"))
      (node (ref "C19") (pin "2") (pinfunction "2_2") (pintype "passive"))
      (node (ref "C2") (pin "2") (pinfunction "2_2") (pintype "passive"))
      (node (ref "C20") (pin "1") (pinfunction "1_1") (pintype "passive"))
      (node (ref "C21") (pin "1") (pinfunction "1_1") (pintype "passive"))
      (node (ref "C22") (pin "2") (pinfunction "2_2") (pintype "passive"))
      (node (ref "C23") (pin "2") (pinfunction "2_2") (pintype "passive"))
      (node (ref "C24") (pin "2") (pinfunction "2_2") (pintype "passive"))
      (node (ref "C25") (pin "2") (pinfunction "2_2") (pintype "passive"))
      (node (ref "C26") (pin "2") (pinfunction "2_2") (pintype "passive"))
      (node (ref "C27") (pin "2") (pinfunction "2_2") (pintype "passive"))
      (node (ref "C3") (pin "2") (pinfunction "2_2") (pintype "passive"))
      (node (ref "C30") (pin "2") (pinfunction "2_2") (pintype "passive"))
      (node (ref "C31") (pin "2") (pinfunction "2_2") (pintype "passive"))
      (node (ref "C32") (pin "2") (pinfunction "2_2") (pintype "passive"))
      (node (ref "C33") (pin "2") (pinfunction "2_2") (pintype "passive"))
      (node (ref "C36") (pin "2") (pinfunction "2_2") (pintype "passive"))
      (node (ref "C37") (pin "2") (pinfunction "2_2") (pintype "passive"))
      (node (ref "C38") (pin "2") (pinfunction "2_2") (pintype "passive"))
      (node (ref "C39") (pin "2") (pinfunction "2_2") (pintype "passive"))
      (node (ref "C4") (pin "2") (pinfunction "2_2") (pintype "passive"))
      (node (ref "C40") (pin "2") (pinfunction "2_2") (pintype "passive"))
      (node (ref "C41") (pin "2") (pinfunction "2_2") (pintype "passive"))
      (node (ref "C42") (pin "2") (pinfunction "2_2") (pintype "passive"))
      (node (ref "C44") (pin "2") (pinfunction "2_2") (pintype "passive"))
      (node (ref "C5") (pin "2") (pinfunction "2_2") (pintype "passive"))
      (node (ref "C53") (pin "2") (pinfunction "2_2") (pintype "passive"))
      (node (ref "C54") (pin "2") (pinfunction "2_2") (pintype "passive"))
      (node (ref "C55") (pin "2") (pinfunction "2_2") (pintype "passive"))
      (node (ref "C56") (pin "2") (pinfunction "2_2") (pintype "passive"))
      (node (ref "C6") (pin "2") (pinfunction "2_2") (pintype "passive"))
      (node (ref "C7") (pin "2") (pinfunction "2_2") (pintype "passive"))
      (node (ref "C9") (pin "2") (pinfunction "2_2") (pintype "passive"))
      (node (ref "DSP_OUT") (pin "1") (pinfunction "GND_1") (pintype "bidirectional"))
      (node (ref "DSP_OUT") (pin "2") (pinfunction "GND_2") (pintype "bidirectional"))
      (node (ref "DSP_OUT") (pin "3") (pinfunction "GND_3") (pintype "bidirectional"))
      (node (ref "DSP_OUT") (pin "4") (pinfunction "GND_4") (pintype "bidirectional"))
      (node (ref "FT232RL") (pin "18") (pinfunction "GND18_18") (pintype "power_in"))
      (node (ref "FT232RL") (pin "21") (pinfunction "GND21_21") (pintype "power_in"))
      (node (ref "FT232RL") (pin "25") (pinfunction "AGND_25") (pintype "power_in"))
      (node (ref "FT232RL") (pin "26") (pinfunction "TEST_26") (pintype "input"))
      (node (ref "FT232RL") (pin "7") (pinfunction "GND7_7") (pintype "power_in"))
      (node (ref "H1") (pin "B2,0") (pinfunction "MOUNT_B2,0") (pintype "passive"))
      (node (ref "H2") (pin "B2,0") (pinfunction "MOUNT_B2,0") (pintype "passive"))
      (node (ref "H3") (pin "B2,0") (pinfunction "MOUNT_B2,0") (pintype "passive"))
      (node (ref "H4") (pin "B2,0") (pinfunction "MOUNT_B2,0") (pintype "passive"))
      (node (ref "L1") (pin "2") (pinfunction "2_2") (pintype "passive"))
      (node (ref "L1") (pin "3") (pinfunction "3_3") (pintype "passive"))
      (node (ref "MIC_IN") (pin "SLEEVE") (pinfunction "SLEEVE_SLEEVE") (pintype "bidirectional"))
      (node (ref "MPQ4420") (pin "4") (pinfunction "GND_4") (pintype "bidirectional"))
      (node (ref "PAM8406") (pin "10") (pinfunction "INR_10") (pintype "input"))
      (node (ref "PAM8406") (pin "11") (pinfunction "GND_11") (pintype "bidirectional"))
      (node (ref "PAM8406") (pin "15") (pinfunction "PGNDR_15") (pintype "bidirectional"))
      (node (ref "PAM8406") (pin "2") (pinfunction "PGNDL_2") (pintype "bidirectional"))
      (node (ref "PCM5122") (pin "16") (pinfunction "ADR2/GPIO2/DOUT_16") (pintype "bidirectional"))
      (node (ref "PCM5122") (pin "17") (pinfunction "MODE1_17") (pintype "bidirectional"))
      (node (ref "PCM5122") (pin "24") (pinfunction "ADR1/MISO/FMT_24") (pintype "input"))
      (node (ref "PCM5122") (pin "27") (pinfunction "DGND_27") (pintype "bidirectional"))
      (node (ref "PIC24FJ1024GA606") (pin "20") (pinfunction "AVSS_20") (pintype "power_in"))
      (node (ref "PIC24FJ1024GA606") (pin "25") (pinfunction "VSS_25") (pintype "power_in"))
      (node (ref "PIC24FJ1024GA606") (pin "41") (pinfunction "VSS_41") (pintype "power_in"))
      (node (ref "PIC24FJ1024GA606") (pin "9") (pinfunction "VSS_9") (pintype "power_in"))
      (node (ref "PICKIT") (pin "4") (pinfunction "4_4") (pintype "bidirectional"))
      (node (ref "PWR") (pin "-") (pinfunction "C_-") (pintype "passive"))
      (node (ref "PWR_IN") (pin "1") (pinfunction "1_1") (pintype "passive"))
      (node (ref "Q1") (pin "2") (pinfunction "S_2") (pintype "bidirectional"))
      (node (ref "Q3") (pin "2") (pinfunction "S_2") (pintype "bidirectional"))
      (node (ref "Q4") (pin "2") (pinfunction "S_2") (pintype "bidirectional"))
      (node (ref "R22") (pin "1") (pinfunction "1_1") (pintype "passive"))
      (node (ref "R26") (pin "1") (pinfunction "1_1") (pintype "passive"))
      (node (ref "R3") (pin "1") (pinfunction "1_1") (pintype "passive"))
      (node (ref "R30") (pin "1") (pinfunction "1_1") (pintype "passive"))
      (node (ref "R32") (pin "1") (pinfunction "1_1") (pintype "passive"))
      (node (ref "R33") (pin "1") (pinfunction "1_1") (pintype "passive"))
      (node (ref "R4") (pin "1") (pinfunction "1_1") (pintype "passive"))
      (node (ref "R9") (pin "1") (pinfunction "1_1") (pintype "passive"))
      (node (ref "RECOVERY") (pin "1") (pinfunction "1_1") (pintype "passive"))
      (node (ref "SH1") (pin "1") (pinfunction "P$1_1") (pintype "bidirectional"))
      (node (ref "TCU_IO") (pin "4") (pinfunction "4_4") (pintype "bidirectional"))
      (node (ref "TH3122") (pin "12") (pinfunction "GND3_12") (pintype "passive"))
      (node (ref "TH3122") (pin "13") (pinfunction "GND4_13") (pintype "passive"))
      (node (ref "TH3122") (pin "3") (pinfunction "VTR_3") (pintype "input"))
      (node (ref "TH3122") (pin "4") (pinfunction "GND1_4") (pintype "passive"))
      (node (ref "TH3122") (pin "5") (pinfunction "GND2_5") (pintype "passive"))
      (node (ref "TH3122") (pin "7") (pinfunction "SI_7") (pintype "bidirectional"))
      (node (ref "TMUX154E") (pin "5") (pinfunction "GND_5") (pintype "power_in"))
      (node (ref "TMUX154E") (pin "9") (pinfunction "EN_9") (pintype "input"))
      (node (ref "USB") (pin "5") (pinfunction "GND_5") (pintype "power_in"))
      (node (ref "USB") (pin "Z1") (pinfunction "SHIELD_Z1") (pintype "bidirectional"))
      (node (ref "USB") (pin "Z2") (pinfunction "SHIELD_Z2") (pintype "bidirectional"))
      (node (ref "USB") (pin "Z3") (pinfunction "SHIELD_Z3") (pintype "bidirectional"))
      (node (ref "USB") (pin "Z4") (pinfunction "SHIELD_Z4") (pintype "bidirectional"))
      (node (ref "WM8804") (pin "18") (pinfunction "DGND_18") (pintype "power_in"))
      (node (ref "WM8804") (pin "8") (pinfunction "PGND_8") (pintype "power_in"))
      (node (ref "XC6210") (pin "2") (pinfunction "GND_2") (pintype "power_in"))
      (node (ref "XC6702") (pin "2") (pinfunction "GND_2") (pintype "power_in"))
    )
    (net (code "17") (name "I2S_CLK") (class "Default")
      (node (ref "PCM5122") (pin "21") (pinfunction "BCK_21") (pintype "input"))
      (node (ref "WM8804") (pin "14") (pinfunction "BCLK_14") (pintype "bidirectional"))
    )
    (net (code "18") (name "I2S_DOUT") (class "Default")
      (node (ref "PCM5122") (pin "22") (pinfunction "DIN_22") (pintype "input"))
      (node (ref "WM8804") (pin "12") (pinfunction "DOUT_12") (pintype "output"))
    )
    (net (code "19") (name "I2S_LRCK") (class "Default")
      (node (ref "PCM5122") (pin "23") (pinfunction "LRCK_23") (pintype "input"))
      (node (ref "WM8804") (pin "15") (pinfunction "LRCLK_15") (pintype "bidirectional"))
    )
    (net (code "20") (name "I2S_SCK") (class "Default")
      (node (ref "PCM5122") (pin "20") (pinfunction "SCK_20") (pintype "input"))
      (node (ref "WM8804") (pin "16") (pinfunction "MCLK_16") (pintype "bidirectional"))
    )
    (net (code "21") (name "IBUS") (class "Default")
      (node (ref "PWR_IN") (pin "3") (pinfunction "3_3") (pintype "passive"))
      (node (ref "R14") (pin "1") (pinfunction "1_1") (pintype "passive"))
    )
    (net (code "22") (name "IBUS_5V") (class "Default")
      (node (ref "C21") (pin "2") (pinfunction "2_2") (pintype "passive"))
      (node (ref "R6") (pin "2") (pinfunction "2_2") (pintype "passive"))
      (node (ref "TH3122") (pin "16") (pinfunction "VCC_16") (pintype "passive"))
    )
    (net (code "23") (name "IBUS_EN") (class "Default")
      (node (ref "PIC24FJ1024GA606") (pin "59") (pinfunction "RF1_59") (pintype "bidirectional"))
      (node (ref "TH3122") (pin "2") (pinfunction "EN_2") (pintype "input"))
    )
    (net (code "24") (name "IBUS_URX") (class "Default")
      (node (ref "PIC24FJ1024GA606") (pin "45") (pinfunction "RP12/PMA14/PMCS1/RD11_45") (pintype "bidirectional"))
      (node (ref "TH3122") (pin "10") (pinfunction "RXD_10") (pintype "output"))
    )
    (net (code "25") (name "IBUS_USTA") (class "Default")
      (node (ref "PIC24FJ1024GA606") (pin "46") (pinfunction "CLC3OUT/RP11/U6CTS/ICM6/RD0_46") (pintype "bidirectional"))
      (node (ref "TH3122") (pin "9") (pinfunction "SEN/STA_9") (pintype "bidirectional"))
    )
    (net (code "26") (name "IBUS_UTX") (class "Default")
      (node (ref "PIC24FJ1024GA606") (pin "44") (pinfunction "RP3/PMA15/PMCS2/RD10_44") (pintype "bidirectional"))
      (node (ref "TH3122") (pin "11") (pinfunction "TXD_11") (pintype "input"))
    )
    (net (code "27") (name "MCU_MCLR") (class "Default")
      (node (ref "PIC24FJ1024GA606") (pin "7") (pinfunction "MCLR_7") (pintype "bidirectional"))
      (node (ref "PICKIT") (pin "6") (pinfunction "6_6") (pintype "bidirectional"))
      (node (ref "R12") (pin "2") (pinfunction "2_2") (pintype "passive"))
    )
    (net (code "28") (name "MCU_PGC") (class "Default")
      (node (ref "PIC24FJ1024GA606") (pin "15") (pinfunction "PGEC1_15") (pintype "bidirectional"))
      (node (ref "PICKIT") (pin "5") (pinfunction "5_5") (pintype "bidirectional"))
    )
    (net (code "29") (name "MCU_PGD") (class "Default")
      (node (ref "PIC24FJ1024GA606") (pin "16") (pinfunction "PGED1_16") (pintype "bidirectional"))
      (node (ref "PICKIT") (pin "3") (pinfunction "3_3") (pintype "bidirectional"))
    )
    (net (code "30") (name "MCU_RECOV") (class "Default")
      (node (ref "PIC24FJ1024GA606") (pin "53") (pinfunction "RP20/PMRD/PMWR/RD5_53") (pintype "bidirectional"))
      (node (ref "R15") (pin "1") (pinfunction "1_1") (pintype "passive"))
      (node (ref "RECOVERY") (pin "2") (pinfunction "2_2") (pintype "passive"))
    )
    (net (code "31") (name "MCU_SCK3") (class "Default")
      (node (ref "PCM5122") (pin "12") (pinfunction "SCL/MC/ATT1_12") (pintype "bidirectional"))
      (node (ref "PIC24FJ1024GA606") (pin "2") (pinfunction "SCL3/IC5/PMD6/RE6_2") (pintype "bidirectional"))
      (node (ref "R31") (pin "2") (pinfunction "2_2") (pintype "passive"))
      (node (ref "WM8804") (pin "1") (pinfunction "SCLK_1") (pintype "input"))
    )
    (net (code "32") (name "MCU_SDA3") (class "Default")
      (node (ref "PCM5122") (pin "11") (pinfunction "SDA/MOSI/ATT2_11") (pintype "bidirectional"))
      (node (ref "PIC24FJ1024GA606") (pin "3") (pinfunction "SDA3/IC6/PMD7/RE7_3") (pintype "bidirectional"))
      (node (ref "R29") (pin "2") (pinfunction "2_2") (pintype "passive"))
      (node (ref "WM8804") (pin "3") (pinfunction "SDIN/HWMODE_3") (pintype "input"))
    )
    (net (code "33") (name "MCU_TEL_MUTE") (class "Default")
      (node (ref "PIC24FJ1024GA606") (pin "62") (pinfunction "PMD2/RE2_62") (pintype "bidirectional"))
      (node (ref "Q1") (pin "1") (pinfunction "G_1") (pintype "bidirectional"))
      (node (ref "R4") (pin "2") (pinfunction "2_2") (pintype "passive"))
    )
    (net (code "34") (name "MCU_TEL_ON") (class "Default")
      (node (ref "PIC24FJ1024GA606") (pin "18") (pinfunction "PGED2/AN7/RP7/U6TX/RB7_18") (pintype "bidirectional"))
      (node (ref "Q3") (pin "1") (pinfunction "G_1") (pintype "bidirectional"))
      (node (ref "R3") (pin "2") (pinfunction "2_2") (pintype "passive"))
    )
    (net (code "35") (name "MCU_URX") (class "Default")
      (node (ref "PIC24FJ1024GA606") (pin "50") (pinfunction "RP23/PMACK1/RD2_50") (pintype "bidirectional"))
      (node (ref "R16") (pin "1") (pinfunction "1_1") (pintype "passive"))
      (node (ref "TMUX154E") (pin "3") (pinfunction "A1_3") (pintype "bidirectional"))
    )
    (net (code "36") (name "MCU_UTX") (class "Default")
      (node (ref "PIC24FJ1024GA606") (pin "49") (pinfunction "RP24/U5TX/ICM4/RD1_49") (pintype "bidirectional"))
      (node (ref "R18") (pin "1") (pinfunction "1_1") (pintype "passive"))
      (node (ref "TMUX154E") (pin "7") (pinfunction "B1_7") (pintype "bidirectional"))
    )
    (net (code "37") (name "Net-(BC127-MIC_BIAS)") (class "Default")
      (node (ref "BC127") (pin "17") (pinfunction "MIC_BIAS_17") (pintype "input"))
      (node (ref "BC127") (pin "21") (pinfunction "MIC_LP_21") (pintype "input"))
      (node (ref "R24") (pin "2") (pinfunction "2_2") (pintype "passive"))
    )
    (net (code "38") (name "Net-(BC127-RST#)") (class "Default")
      (node (ref "BC127") (pin "44") (pinfunction "RST#_44") (pintype "input"))
      (node (ref "R25") (pin "1") (pinfunction "1_1") (pintype "passive"))
    )
    (net (code "39") (name "Net-(BC127-VREGEN)") (class "Default")
      (node (ref "BC127") (pin "28") (pinfunction "VREGEN_28") (pintype "output"))
      (node (ref "Q4") (pin "3") (pinfunction "D_3") (pintype "bidirectional"))
      (node (ref "R23") (pin "2") (pinfunction "2_2") (pintype "passive"))
    )
    (net (code "40") (name "Net-(C8-Pad1)") (class "Default")
      (node (ref "C8") (pin "1") (pinfunction "1_1") (pintype "passive"))
      (node (ref "R7") (pin "2") (pinfunction "2_2") (pintype "passive"))
    )
    (net (code "41") (name "Net-(C18-Pad1)") (class "Default")
      (node (ref "C18") (pin "1") (pinfunction "1_1") (pintype "passive"))
      (node (ref "R12") (pin "1") (pinfunction "1_1") (pintype "passive"))
      (node (ref "R13") (pin "2") (pinfunction "2_2") (pintype "passive"))
    )
    (net (code "42") (name "Net-(C29-Pad2)") (class "Default")
      (node (ref "C29") (pin "2") (pinfunction "2_2") (pintype "passive"))
      (node (ref "R26") (pin "2") (pinfunction "2_2") (pintype "passive"))
      (node (ref "R27") (pin "1") (pinfunction "1_1") (pintype "passive"))
    )
    (net (code "43") (name "Net-(C43-Pad1)") (class "Default")
      (node (ref "C43") (pin "1") (pinfunction "1_1") (pintype "passive"))
      (node (ref "FB3") (pin "2") (pinfunction "2_2") (pintype "bidirectional"))
    )
    (net (code "44") (name "Net-(C43-Pad2)") (class "Default")
      (node (ref "C43") (pin "2") (pinfunction "2_2") (pintype "passive"))
      (node (ref "R35") (pin "1") (pinfunction "1_1") (pintype "passive"))
    )
    (net (code "45") (name "Net-(F1-IN)") (class "Default")
      (node (ref "F1") (pin "OUT") (pinfunction "IN_OUT") (pintype "bidirectional"))
      (node (ref "L1") (pin "1") (pinfunction "1_1") (pintype "passive"))
    )
    (net (code "46") (name "Net-(F1-OUT)") (class "Default")
      (node (ref "D1") (pin "C") (pinfunction "C_C") (pintype "passive"))
      (node (ref "F1") (pin "IN") (pinfunction "OUT_IN") (pintype "bidirectional"))
    )
    (net (code "47") (name "Net-(FT232RL-3V3OUT)") (class "Default")
      (node (ref "C27") (pin "1") (pinfunction "1_1") (pintype "passive"))
      (node (ref "FT232RL") (pin "17") (pinfunction "3V3OUT_17") (pintype "output"))
      (node (ref "FT232RL") (pin "4") (pinfunction "VCCIO_4") (pintype "power_in"))
    )
    (net (code "48") (name "Net-(FT232RL-RXLED)") (class "Default")
      (node (ref "FT232RL") (pin "22") (pinfunction "RXLED_22") (pintype "input"))
      (node (ref "TX") (pin "-") (pinfunction "C_-") (pintype "passive"))
    )
    (net (code "49") (name "Net-(FT232RL-TXLED)") (class "Default")
      (node (ref "FT232RL") (pin "23") (pinfunction "TXLED_23") (pintype "input"))
      (node (ref "RX") (pin "-") (pinfunction "C_-") (pintype "passive"))
    )
    (net (code "50") (name "Net-(MPQ4420-BS)") (class "Default")
      (node (ref "MPQ4420") (pin "5") (pinfunction "BS_5") (pintype "bidirectional"))
      (node (ref "R7") (pin "1") (pinfunction "1_1") (pintype "passive"))
    )
    (net (code "51") (name "Net-(MPQ4420-EN)") (class "Default")
      (node (ref "MPQ4420") (pin "6") (pinfunction "EN_6") (pintype "bidirectional"))
      (node (ref "R6") (pin "1") (pinfunction "1_1") (pintype "passive"))
    )
    (net (code "52") (name "Net-(MPQ4420-FB)") (class "Default")
      (node (ref "MPQ4420") (pin "8") (pinfunction "FB_8") (pintype "bidirectional"))
      (node (ref "R8") (pin "2") (pinfunction "2_2") (pintype "passive"))
    )
    (net (code "53") (name "Net-(MPQ4420-PG)") (class "Default")
      (node (ref "MPQ4420") (pin "1") (pinfunction "PG_1") (pintype "bidirectional"))
      (node (ref "R5") (pin "1") (pinfunction "1_1") (pintype "passive"))
    )
    (net (code "54") (name "Net-(MPQ4420-SW)") (class "Default")
      (node (ref "C8") (pin "2") (pinfunction "2_2") (pintype "passive"))
      (node (ref "L2") (pin "1") (pinfunction "1_1") (pintype "passive"))
      (node (ref "MPQ4420") (pin "3") (pinfunction "SW_3") (pintype "bidirectional"))
    )
    (net (code "55") (name "Net-(MPQ4420-VCC)") (class "Default")
      (node (ref "C7") (pin "1") (pinfunction "1_1") (pintype "passive"))
      (node (ref "MPQ4420") (pin "7") (pinfunction "VCC_7") (pintype "bidirectional"))
      (node (ref "R5") (pin "2") (pinfunction "2_2") (pintype "passive"))
    )
    (net (code "56") (name "Net-(PAM8406-INL)") (class "Default")
      (node (ref "PAM8406") (pin "7") (pinfunction "INL_7") (pintype "input"))
      (node (ref "R35") (pin "2") (pinfunction "2_2") (pintype "passive"))
    )
    (net (code "57") (name "Net-(PAM8406-OUT_L+)") (class "Default")
      (node (ref "FB1") (pin "1") (pinfunction "1_1") (pintype "bidirectional"))
      (node (ref "PAM8406") (pin "1") (pinfunction "OUT_L+_1") (pintype "output"))
    )
    (net (code "58") (name "Net-(PAM8406-OUT_L-)") (class "Default")
      (node (ref "FB2") (pin "1") (pinfunction "1_1") (pintype "bidirectional"))
      (node (ref "PAM8406") (pin "3") (pinfunction "OUT_L-_3") (pintype "output"))
    )
    (net (code "59") (name "Net-(PAM8406-VREF)") (class "Default")
      (node (ref "C44") (pin "1") (pinfunction "1_1") (pintype "passive"))
      (node (ref "PAM8406") (pin "8") (pinfunction "VREF_8") (pintype "output"))
    )
    (net (code "60") (name "Net-(PCM5122-CAPM)") (class "Default")
      (node (ref "C50") (pin "2") (pinfunction "2_2") (pintype "passive"))
      (node (ref "PCM5122") (pin "4") (pinfunction "CAPM_4") (pintype "output"))
    )
    (net (code "61") (name "Net-(PCM5122-CAPP)") (class "Default")
      (node (ref "C50") (pin "1") (pinfunction "1_1") (pintype "passive"))
      (node (ref "PCM5122") (pin "2") (pinfunction "CAPP_2") (pintype "output"))
    )
    (net (code "62") (name "Net-(PCM5122-LDOO)") (class "Default")
      (node (ref "C55") (pin "1") (pinfunction "1_1") (pintype "passive"))
      (node (ref "C56") (pin "1") (pinfunction "1_1") (pintype "passive"))
      (node (ref "PCM5122") (pin "26") (pinfunction "LDOO_26") (pintype "power_in"))
    )
    (net (code "63") (name "Net-(PCM5122-OUTR)") (class "Default")
      (node (ref "PCM5122") (pin "7") (pinfunction "OUTR_7") (pintype "output"))
      (node (ref "R36") (pin "1") (pinfunction "1_1") (pintype "passive"))
    )
    (net (code "64") (name "Net-(PCM5122-VNEG)") (class "Default")
      (node (ref "C49") (pin "2") (pinfunction "2_2") (pintype "passive"))
      (node (ref "PCM5122") (pin "5") (pinfunction "VNEG_5") (pintype "output"))
    )
    (net (code "65") (name "Net-(PIC24FJ1024GA606-PMD0{slash}RE0)") (class "Default")
      (node (ref "PIC24FJ1024GA606") (pin "60") (pinfunction "PMD0/RE0_60") (pintype "bidirectional"))
      (node (ref "R19") (pin "2") (pinfunction "2_2") (pintype "passive"))
    )
    (net (code "66") (name "Net-(PIC24FJ1024GA606-VCAP)") (class "Default")
      (node (ref "C19") (pin "1") (pinfunction "1_1") (pintype "passive"))
      (node (ref "PIC24FJ1024GA606") (pin "56") (pinfunction "VCAP_56") (pintype "passive"))
    )
    (net (code "67") (name "Net-(PWR-A)") (class "Default")
      (node (ref "PWR") (pin "+") (pinfunction "A_+") (pintype "passive"))
      (node (ref "R19") (pin "1") (pinfunction "1_1") (pintype "passive"))
    )
    (net (code "68") (name "Net-(Q2-D)") (class "Default")
      (node (ref "Q2") (pin "3") (pinfunction "D_3") (pintype "bidirectional"))
      (node (ref "R1") (pin "1") (pinfunction "1_1") (pintype "passive"))
    )
    (net (code "69") (name "Net-(Q2-G)") (class "Default")
      (node (ref "Q2") (pin "1") (pinfunction "G_1") (pintype "bidirectional"))
      (node (ref "Q3") (pin "3") (pinfunction "D_3") (pintype "bidirectional"))
      (node (ref "R2") (pin "1") (pinfunction "1_1") (pintype "passive"))
    )
    (net (code "70") (name "Net-(Q4-G)") (class "Default")
      (node (ref "C28") (pin "2") (pinfunction "2_2") (pintype "passive"))
      (node (ref "Q4") (pin "1") (pinfunction "G_1") (pintype "bidirectional"))
      (node (ref "R22") (pin "2") (pinfunction "2_2") (pintype "passive"))
    )
    (net (code "71") (name "Net-(R10-Pad1)") (class "Default")
      (node (ref "R10") (pin "1") (pinfunction "1_1") (pintype "passive"))
      (node (ref "R8") (pin "1") (pinfunction "1_1") (pintype "passive"))
      (node (ref "R9") (pin "2") (pinfunction "2_2") (pintype "passive"))
    )
    (net (code "72") (name "Net-(RX-A)") (class "Default")
      (node (ref "R20") (pin "1") (pinfunction "1_1") (pintype "passive"))
      (node (ref "RX") (pin "+") (pinfunction "A_+") (pintype "passive"))
    )
    (net (code "73") (name "Net-(TH3122-IBUS)") (class "Default")
      (node (ref "C22") (pin "1") (pinfunction "1_1") (pintype "passive"))
      (node (ref "R14") (pin "2") (pinfunction "2_2") (pintype "passive"))
      (node (ref "TH3122") (pin "6") (pinfunction "IBUS_6") (pintype "bidirectional"))
    )
    (net (code "74") (name "Net-(TX-A)") (class "Default")
      (node (ref "R21") (pin "1") (pinfunction "1_1") (pintype "passive"))
      (node (ref "TX") (pin "+") (pinfunction "A_+") (pintype "passive"))
    )
    (net (code "75") (name "Net-(WM8804-CSB{slash}GPO1)") (class "Default")
      (node (ref "R32") (pin "2") (pinfunction "2_2") (pintype "passive"))
      (node (ref "WM8804") (pin "5") (pinfunction "CSB/GPO1_5") (pintype "input"))
    )
    (net (code "76") (name "Net-(WM8804-GPO0{slash}SWIFMODE)") (class "Default")
      (node (ref "R30") (pin "2") (pinfunction "2_2") (pintype "passive"))
      (node (ref "WM8804") (pin "2") (pinfunction "GPO0/SWIFMODE_2") (pintype "output"))
    )
    (net (code "77") (name "Net-(WM8804-RESETB)") (class "Default")
      (node (ref "R28") (pin "2") (pinfunction "2_2") (pintype "passive"))
      (node (ref "WM8804") (pin "6") (pinfunction "RESETB_6") (pintype "input"))
    )
    (net (code "78") (name "Net-(WM8804-RXO)") (class "Default")
      (node (ref "C34") (pin "1") (pinfunction "1_1") (pintype "passive"))
      (node (ref "WM8804") (pin "20") (pinfunction "RXO_20") (pintype "input"))
    )
    (net (code "79") (name "Net-(WM8804-TXO)") (class "Default")
      (node (ref "R27") (pin "2") (pinfunction "2_2") (pintype "passive"))
      (node (ref "WM8804") (pin "17") (pinfunction "TXO_17") (pintype "output"))
    )
    (net (code "80") (name "Net-(WM8804-XIN)") (class "Default")
      (node (ref "C31") (pin "1") (pinfunction "1_1") (pintype "passive"))
      (node (ref "WM8804") (pin "11") (pinfunction "XIN_11") (pintype "bidirectional"))
      (node (ref "X1") (pin "2") (pinfunction "2_2") (pintype "passive"))
    )
    (net (code "81") (name "Net-(WM8804-XOP)") (class "Default")
      (node (ref "C32") (pin "1") (pinfunction "1_1") (pintype "passive"))
      (node (ref "WM8804") (pin "10") (pinfunction "XOP_10") (pintype "bidirectional"))
      (node (ref "X1") (pin "1") (pinfunction "1_1") (pintype "passive"))
    )
    (net (code "82") (name "SPDIF_OUT") (class "Default")
      (node (ref "C29") (pin "1") (pinfunction "1_1") (pintype "passive"))
      (node (ref "DSP_OUT") (pin "P$1") (pinfunction "1_P$1") (pintype "passive"))
    )
    (net (code "83") (name "SPKR_OUT_L") (class "Default")
      (node (ref "C46") (pin "1") (pinfunction "1_1") (pintype "passive"))
      (node (ref "R37") (pin "2") (pinfunction "2_2") (pintype "passive"))
      (node (ref "SPKR_OUT") (pin "1") (pinfunction "1_1") (pintype "bidirectional"))
    )
    (net (code "84") (name "SPKR_OUT_R") (class "Default")
      (node (ref "C45") (pin "1") (pinfunction "1_1") (pintype "passive"))
      (node (ref "R36") (pin "2") (pinfunction "2_2") (pintype "passive"))
      (node (ref "SPKR_OUT") (pin "4") (pinfunction "4_4") (pintype "bidirectional"))
    )
    (net (code "85") (name "SYS_DTR") (class "Default")
      (node (ref "FT232RL") (pin "2") (pinfunction "DTR_2") (pintype "output"))
      (node (ref "PIC24FJ1024GA606") (pin "52") (pinfunction "RP25/PMWR/PMENB/RD4_52") (pintype "bidirectional"))
    )
    (net (code "86") (name "SYS_UART_SEL") (class "Default")
      (node (ref "PIC24FJ1024GA606") (pin "51") (pinfunction "RP22/ICM7/PMBE0/RD3_51") (pintype "bidirectional"))
      (node (ref "R17") (pin "2") (pinfunction "2_2") (pintype "passive"))
      (node (ref "TMUX154E") (pin "1") (pinfunction "SEL_1") (pintype "bidirectional"))
    )
    (net (code "87") (name "SYS_URX") (class "Default")
      (node (ref "FT232RL") (pin "5") (pinfunction "RXD_5") (pintype "input"))
      (node (ref "TMUX154E") (pin "6") (pinfunction "B_6") (pintype "bidirectional"))
    )
    (net (code "88") (name "SYS_USB_DN") (class "Default")
      (node (ref "FT232RL") (pin "16") (pinfunction "USBDM_16") (pintype "bidirectional"))
      (node (ref "USB") (pin "2") (pinfunction "D-_2") (pintype "bidirectional"))
    )
    (net (code "89") (name "SYS_USB_DP") (class "Default")
      (node (ref "FT232RL") (pin "15") (pinfunction "USBDP_15") (pintype "bidirectional"))
      (node (ref "USB") (pin "3") (pinfunction "D+_3") (pintype "bidirectional"))
    )
    (net (code "90") (name "SYS_UTX") (class "Default")
      (node (ref "FT232RL") (pin "1") (pinfunction "TXD_1") (pintype "output"))
      (node (ref "TMUX154E") (pin "4") (pinfunction "A_4") (pintype "bidirectional"))
    )
    (net (code "91") (name "TEL_AMP_SHDN") (class "Default")
      (node (ref "PAM8406") (pin "12") (pinfunction "SHDN_12") (pintype "input"))
      (node (ref "PIC24FJ1024GA606") (pin "63") (pinfunction "CTED9/PMD3/RE3_63") (pintype "bidirectional"))
    )
    (net (code "92") (name "TEL_MIC_L_OUT") (class "Default")
      (node (ref "C35") (pin "2") (pinfunction "2_2") (pintype "passive"))
      (node (ref "R34") (pin "2") (pinfunction "2_2") (pintype "passive"))
      (node (ref "TCU_IO") (pin "3") (pinfunction "3_3") (pintype "bidirectional"))
    )
    (net (code "93") (name "TEL_MUTE_IO") (class "Default")
      (node (ref "Q1") (pin "3") (pinfunction "D_3") (pintype "bidirectional"))
      (node (ref "TCU_IO") (pin "6") (pinfunction "6_6") (pintype "bidirectional"))
    )
    (net (code "94") (name "TEL_ON_IO") (class "Default")
      (node (ref "R1") (pin "2") (pinfunction "2_2") (pintype "passive"))
      (node (ref "TCU_IO") (pin "5") (pinfunction "5_5") (pintype "bidirectional"))
    )
    (net (code "95") (name "TEL_OUT_L+") (class "Default")
      (node (ref "C39") (pin "1") (pinfunction "1_1") (pintype "passive"))
      (node (ref "FB1") (pin "2") (pinfunction "2_2") (pintype "bidirectional"))
      (node (ref "TCU_IO") (pin "1") (pinfunction "1_1") (pintype "bidirectional"))
    )
    (net (code "96") (name "TEL_OUT_L-") (class "Default")
      (node (ref "C40") (pin "1") (pinfunction "1_1") (pintype "passive"))
      (node (ref "FB2") (pin "2") (pinfunction "2_2") (pintype "bidirectional"))
      (node (ref "TCU_IO") (pin "2") (pinfunction "2_2") (pintype "bidirectional"))
    )
    (net (code "97") (name "USB_5V") (class "Default")
      (node (ref "D2") (pin "A") (pinfunction "A_A") (pintype "passive"))
      (node (ref "USB") (pin "1") (pinfunction "VBUS_1") (pintype "power_in"))
    )
    (net (code "98") (name "VBAT") (class "Default")
      (node (ref "D1") (pin "A") (pinfunction "A_A") (pintype "passive"))
      (node (ref "PWR_IN") (pin "2") (pinfunction "2_2") (pintype "passive"))
    )
    (net (code "99") (name "VBAT_SENSE") (class "Default")
      (node (ref "BC127") (pin "31") (pinfunction "VBAT_SENSE_31") (pintype "power_in"))
    )
    (net (code "100") (name "VCHG") (class "Default")
      (node (ref "BC127") (pin "30") (pinfunction "VCHG_30") (pintype "power_in"))
    )
    (net (code "101") (name "VIN") (class "Default")
      (node (ref "C1") (pin "1") (pinfunction "1_1") (pintype "passive"))
      (node (ref "C10") (pin "1") (pinfunction "1_1") (pintype "passive"))
      (node (ref "C11") (pin "1") (pinfunction "1_1") (pintype "passive"))
      (node (ref "C23") (pin "1") (pinfunction "1_1") (pintype "passive"))
      (node (ref "C6") (pin "1") (pinfunction "1_1") (pintype "passive"))
      (node (ref "C9") (pin "1") (pinfunction "1_1") (pintype "passive"))
      (node (ref "L1") (pin "4") (pinfunction "4_4") (pintype "passive"))
      (node (ref "MPQ4420") (pin "2") (pinfunction "IN_2") (pintype "bidirectional"))
      (node (ref "TH3122") (pin "1") (pinfunction "VS_1") (pintype "power_in"))
      (node (ref "XC6702") (pin "3") (pinfunction "CE_3") (pintype "power_in"))
      (node (ref "XC6702") (pin "5") (pinfunction "VIN_5") (pintype "power_in"))
    )
    (net (code "102") (name "unconnected-(BC127-AIO-Pad12)") (class "Default")
      (node (ref "BC127") (pin "12") (pinfunction "AIO_12") (pintype "bidirectional"))
    )
    (net (code "103") (name "unconnected-(BC127-CAP_SENSE_1-Pad7)") (class "Default")
      (node (ref "BC127") (pin "7") (pinfunction "CAP_SENSE_1_7") (pintype "input"))
    )
    (net (code "104") (name "unconnected-(BC127-CAP_SENSE_2-Pad8)") (class "Default")
      (node (ref "BC127") (pin "8") (pinfunction "CAP_SENSE_2_8") (pintype "input"))
    )
    (net (code "105") (name "unconnected-(BC127-CAP_SENSE_3-Pad9)") (class "Default")
      (node (ref "BC127") (pin "9") (pinfunction "CAP_SENSE_3_9") (pintype "input"))
    )
    (net (code "106") (name "unconnected-(BC127-CAP_SENSE_4-Pad10)") (class "Default")
      (node (ref "BC127") (pin "10") (pinfunction "CAP_SENSE_4_10") (pintype "input"))
    )
    (net (code "107") (name "unconnected-(BC127-LED_0-Pad37)") (class "Default")
      (node (ref "BC127") (pin "37") (pinfunction "LED_0_37") (pintype "output"))
    )
    (net (code "108") (name "unconnected-(BC127-LED_1-Pad38)") (class "Default")
      (node (ref "BC127") (pin "38") (pinfunction "LED_1_38") (pintype "output"))
    )
    (net (code "109") (name "unconnected-(BC127-LED_2-Pad39)") (class "Default")
      (node (ref "BC127") (pin "39") (pinfunction "LED_2_39") (pintype "output"))
    )
    (net (code "110") (name "unconnected-(BC127-MIC_RN-Pad18)") (class "Default")
      (node (ref "BC127") (pin "18") (pinfunction "MIC_RN_18") (pintype "input"))
    )
    (net (code "111") (name "unconnected-(BC127-MIC_RP-Pad19)") (class "Default")
      (node (ref "BC127") (pin "19") (pinfunction "MIC_RP_19") (pintype "input"))
    )
    (net (code "112") (name "unconnected-(BC127-PCM1_CLK-Pad47)") (class "Default")
      (node (ref "BC127") (pin "47") (pinfunction "PCM1_CLK_47") (pintype "bidirectional"))
    )
    (net (code "113") (name "unconnected-(BC127-PCM1_IN-Pad49)") (class "Default")
      (node (ref "BC127") (pin "49") (pinfunction "PCM1_IN_49") (pintype "bidirectional"))
    )
    (net (code "114") (name "unconnected-(BC127-PCM1_SYNC-Pad46)") (class "Default")
      (node (ref "BC127") (pin "46") (pinfunction "PCM1_SYNC_46") (pintype "bidirectional"))
    )
    (net (code "115") (name "unconnected-(BC127-PIO_0-Pad23)") (class "Default")
      (node (ref "BC127") (pin "23") (pinfunction "PIO_0_23") (pintype "bidirectional"))
    )
    (net (code "116") (name "unconnected-(BC127-PIO_1-Pad24)") (class "Default")
      (node (ref "BC127") (pin "24") (pinfunction "PIO_1_24") (pintype "bidirectional"))
    )
    (net (code "117") (name "unconnected-(BC127-PIO_2-Pad50)") (class "Default")
      (node (ref "BC127") (pin "50") (pinfunction "PIO_2_50") (pintype "bidirectional"))
    )
    (net (code "118") (name "unconnected-(BC127-PIO_3-Pad51)") (class "Default")
      (node (ref "BC127") (pin "51") (pinfunction "PIO_3_51") (pintype "bidirectional"))
    )
    (net (code "119") (name "unconnected-(BC127-PIO_4{slash}PCM2_IN-Pad26)") (class "Default")
      (node (ref "BC127") (pin "26") (pinfunction "PIO_4/PCM2_IN_26") (pintype "bidirectional"))
    )
    (net (code "120") (name "unconnected-(BC127-PIO_6{slash}PCM2_SYNC-Pad5)") (class "Default")
      (node (ref "BC127") (pin "5") (pinfunction "PIO_6/PCM2_SYNC_5") (pintype "bidirectional"))
    )
    (net (code "121") (name "unconnected-(BC127-PIO_7{slash}PCM2_CLK-Pad6)") (class "Default")
      (node (ref "BC127") (pin "6") (pinfunction "PIO_7/PCM2_CLK_6") (pintype "bidirectional"))
    )
    (net (code "122") (name "unconnected-(BC127-SPKR_LN-Pad13)") (class "Default")
      (node (ref "BC127") (pin "13") (pinfunction "SPKR_LN_13") (pintype "output"))
    )
    (net (code "123") (name "unconnected-(BC127-SPKR_LP-Pad14)") (class "Default")
      (node (ref "BC127") (pin "14") (pinfunction "SPKR_LP_14") (pintype "output"))
    )
    (net (code "124") (name "unconnected-(BC127-SPKR_RN-Pad15)") (class "Default")
      (node (ref "BC127") (pin "15") (pinfunction "SPKR_RN_15") (pintype "output"))
    )
    (net (code "125") (name "unconnected-(BC127-SPKR_RP-Pad16)") (class "Default")
      (node (ref "BC127") (pin "16") (pinfunction "SPKR_RP_16") (pintype "output"))
    )
    (net (code "126") (name "unconnected-(BC127-UART_CTS-Pad40)") (class "Default")
      (node (ref "BC127") (pin "40") (pinfunction "UART_CTS_40") (pintype "input"))
    )
    (net (code "127") (name "unconnected-(BC127-UART_RTS-Pad43)") (class "Default")
      (node (ref "BC127") (pin "43") (pinfunction "UART_RTS_43") (pintype "output"))
    )
    (net (code "128") (name "unconnected-(BC127-USB_N-Pad35)") (class "Default")
      (node (ref "BC127") (pin "35") (pinfunction "USB_N_35") (pintype "bidirectional"))
    )
    (net (code "129") (name "unconnected-(BC127-USB_P-Pad36)") (class "Default")
      (node (ref "BC127") (pin "36") (pinfunction "USB_P_36") (pintype "bidirectional"))
    )
    (net (code "130") (name "unconnected-(FT232RL-CTS-Pad11)") (class "Default")
      (node (ref "FT232RL") (pin "11") (pinfunction "CTS_11") (pintype "input"))
    )
    (net (code "131") (name "unconnected-(FT232RL-DCD-Pad10)") (class "Default")
      (node (ref "FT232RL") (pin "10") (pinfunction "DCD_10") (pintype "input"))
    )
    (net (code "132") (name "unconnected-(FT232RL-DSR-Pad9)") (class "Default")
      (node (ref "FT232RL") (pin "9") (pinfunction "DSR_9") (pintype "input"))
    )
    (net (code "133") (name "unconnected-(FT232RL-OSCI-Pad27)") (class "Default")
      (node (ref "FT232RL") (pin "27") (pinfunction "OSCI_27") (pintype "input"))
    )
    (net (code "134") (name "unconnected-(FT232RL-OSCO-Pad28)") (class "Default")
      (node (ref "FT232RL") (pin "28") (pinfunction "OSCO_28") (pintype "output"))
    )
    (net (code "135") (name "unconnected-(FT232RL-PWREN-Pad14)") (class "Default")
      (node (ref "FT232RL") (pin "14") (pinfunction "PWREN_14") (pintype "input"))
    )
    (net (code "136") (name "unconnected-(FT232RL-RESET-Pad19)") (class "Default")
      (node (ref "FT232RL") (pin "19") (pinfunction "RESET_19") (pintype "input"))
    )
    (net (code "137") (name "unconnected-(FT232RL-RI-Pad6)") (class "Default")
      (node (ref "FT232RL") (pin "6") (pinfunction "RI_6") (pintype "input"))
    )
    (net (code "138") (name "unconnected-(FT232RL-RTS-Pad3)") (class "Default")
      (node (ref "FT232RL") (pin "3") (pinfunction "RTS_3") (pintype "output"))
    )
    (net (code "139") (name "unconnected-(FT232RL-SLEEP-Pad12)") (class "Default")
      (node (ref "FT232RL") (pin "12") (pinfunction "SLEEP_12") (pintype "input"))
    )
    (net (code "140") (name "unconnected-(FT232RL-TXDEN-Pad13)") (class "Default")
      (node (ref "FT232RL") (pin "13") (pinfunction "TXDEN_13") (pintype "input"))
    )
    (net (code "141") (name "unconnected-(MIC_IN-RIGHT-PadRING)") (class "Default")
      (node (ref "MIC_IN") (pin "RING") (pinfunction "RIGHT_RING") (pintype "bidirectional"))
    )
    (net (code "142") (name "unconnected-(PAM8406-MUTE-Pad5)") (class "Default")
      (node (ref "PAM8406") (pin "5") (pinfunction "MUTE_5") (pintype "input"))
    )
    (net (code "143") (name "unconnected-(PAM8406-OUT_R+-Pad16)") (class "Default")
      (node (ref "PAM8406") (pin "16") (pinfunction "OUT_R+_16") (pintype "output"))
    )
    (net (code "144") (name "unconnected-(PAM8406-OUT_R--Pad14)") (class "Default")
      (node (ref "PAM8406") (pin "14") (pinfunction "OUT_R-_14") (pintype "output"))
    )
    (net (code "145") (name "unconnected-(PCM5122-GPIO3{slash}AGNS-Pad15)") (class "Default")
      (node (ref "PCM5122") (pin "15") (pinfunction "GPIO3/AGNS_15") (pintype "bidirectional"))
    )
    (net (code "146") (name "unconnected-(PCM5122-GPIO4{slash}MAST-Pad14)") (class "Default")
      (node (ref "PCM5122") (pin "14") (pinfunction "GPIO4/MAST_14") (pintype "bidirectional"))
    )
    (net (code "147") (name "unconnected-(PCM5122-GPIO5{slash}ATT0-Pad13)") (class "Default")
      (node (ref "PCM5122") (pin "13") (pinfunction "GPIO5/ATT0_13") (pintype "bidirectional"))
    )
    (net (code "148") (name "unconnected-(PCM5122-GPIO6{slash}FLT-Pad19)") (class "Default")
      (node (ref "PCM5122") (pin "19") (pinfunction "GPIO6/FLT_19") (pintype "input"))
    )
    (net (code "149") (name "unconnected-(PIC24FJ1024GA606-AN2{slash}CTCMP{slash}C2INB{slash}RP13{slash}CTED13{slash}RB2-Pad14)") (class "Default")
      (node (ref "PIC24FJ1024GA606") (pin "14") (pinfunction "AN2/CTCMP/C2INB/RP13/CTED13/RB2_14") (pintype "bidirectional"))
    )
    (net (code "150") (name "unconnected-(PIC24FJ1024GA606-AN3{slash}C2INA{slash}RB3-Pad13)") (class "Default")
      (node (ref "PIC24FJ1024GA606") (pin "13") (pinfunction "AN3/C2INA/RB3_13") (pintype "bidirectional"))
    )
    (net (code "151") (name "unconnected-(PIC24FJ1024GA606-AN8{slash}RP8{slash}PWRGT{slash}RB8-Pad21)") (class "Default")
      (node (ref "PIC24FJ1024GA606") (pin "21") (pinfunction "AN8/RP8/PWRGT/RB8_21") (pintype "bidirectional"))
    )
    (net (code "152") (name "unconnected-(PIC24FJ1024GA606-AN9{slash}TMPR{slash}RP9{slash}T1CK{slash}PMA7{slash}RB9-Pad22)") (class "Default")
      (node (ref "PIC24FJ1024GA606") (pin "22") (pinfunction "AN9/TMPR/RP9/T1CK/PMA7/RB9_22") (pintype "bidirectional"))
    )
    (net (code "153") (name "unconnected-(PIC24FJ1024GA606-AN14{slash}RP14{slash}CTED5{slash}CTPLS{slash}PMA1{slash}PMALH{slash}RB14-Pad29)") (class "Default")
      (node (ref "PIC24FJ1024GA606") (pin "29") (pinfunction "AN14/RP14/CTED5/CTPLS/PMA1/PMALH/RB14_29") (pintype "bidirectional"))
    )
    (net (code "154") (name "unconnected-(PIC24FJ1024GA606-AN15{slash}RP29{slash}CTED6{slash}PMA0{slash}PMALL{slash}RB15-Pad30)") (class "Default")
      (node (ref "PIC24FJ1024GA606") (pin "30") (pinfunction "AN15/RP29/CTED6/PMA0/PMALL/RB15_30") (pintype "bidirectional"))
    )
    (net (code "155") (name "unconnected-(PIC24FJ1024GA606-C1INC{slash}C2INC{slash}C3INC{slash}RP27{slash}OCM2B{slash}PMA2{slash}PMALU{slash}RG9-Pad8)") (class "Default")
      (node (ref "PIC24FJ1024GA606") (pin "8") (pinfunction "C1INC/C2INC/C3INC/RP27/OCM2B/PMA2/PMALU/RG9_8") (pintype "bidirectional"))
    )
    (net (code "156") (name "unconnected-(PIC24FJ1024GA606-C2IND{slash}RP19{slash}ICM2{slash}OCM2A{slash}PMA3{slash}RG8-Pad6)") (class "Default")
      (node (ref "PIC24FJ1024GA606") (pin "6") (pinfunction "C2IND/RP19/ICM2/OCM2A/PMA3/RG8_6") (pintype "bidirectional"))
    )
    (net (code "157") (name "unconnected-(PIC24FJ1024GA606-C3INA{slash}U5RTS{slash}U5BCLK{slash}OC5{slash}RD7-Pad55)") (class "Default")
      (node (ref "PIC24FJ1024GA606") (pin "55") (pinfunction "C3INA/U5RTS/U5BCLK/OC5/RD7_55") (pintype "bidirectional"))
    )
    (net (code "158") (name "unconnected-(PIC24FJ1024GA606-C3INB{slash}U5RX{slash}OC4{slash}RD6-Pad54)") (class "Default")
      (node (ref "PIC24FJ1024GA606") (pin "54") (pinfunction "C3INB/U5RX/OC4/RD6_54") (pintype "bidirectional"))
    )
    (net (code "159") (name "unconnected-(PIC24FJ1024GA606-IC4{slash}CTED4{slash}PMD5{slash}RE5-Pad1)") (class "Default")
      (node (ref "PIC24FJ1024GA606") (pin "1") (pinfunction "IC4/CTED4/PMD5/RE5_1") (pintype "bidirectional"))
    )
    (net (code "160") (name "unconnected-(PIC24FJ1024GA606-INT0{slash}RF6-Pad35)") (class "Default")
      (node (ref "PIC24FJ1024GA606") (pin "35") (pinfunction "INT0/RF6_35") (pintype "bidirectional"))
    )
    (net (code "161") (name "unconnected-(PIC24FJ1024GA606-N{slash}C-Pad57)") (class "Default")
      (node (ref "PIC24FJ1024GA606") (pin "57") (pinfunction "N/C_57") (pintype "no_connect"))
    )
    (net (code "162") (name "unconnected-(PIC24FJ1024GA606-OSCI{slash}CLKI{slash}RC12-Pad39)") (class "Default")
      (node (ref "PIC24FJ1024GA606") (pin "39") (pinfunction "OSCI/CLKI/RC12_39") (pintype "bidirectional"))
    )
    (net (code "163") (name "unconnected-(PIC24FJ1024GA606-OSCO{slash}CLKO{slash}RC15-Pad40)") (class "Default")
      (node (ref "PIC24FJ1024GA606") (pin "40") (pinfunction "OSCO/CLKO/RC15_40") (pintype "bidirectional"))
    )
    (net (code "164") (name "unconnected-(PIC24FJ1024GA606-PGEC2{slash}AN6{slash}RP6{slash}RB6-Pad17)") (class "Default")
      (node (ref "PIC24FJ1024GA606") (pin "17") (pinfunction "PGEC2/AN6/RP6/RB6_17") (pintype "bidirectional"))
    )
    (net (code "165") (name "unconnected-(PIC24FJ1024GA606-PGEC3{slash}AN5{slash}C1INA{slash}RP18{slash}ICM3{slash}OCM3A{slash}RB5-Pad11)") (class "Default")
      (node (ref "PIC24FJ1024GA606") (pin "11") (pinfunction "PGEC3/AN5/C1INA/RP18/ICM3/OCM3A/RB5_11") (pintype "bidirectional"))
    )
    (net (code "166") (name "unconnected-(PIC24FJ1024GA606-PGED3{slash}AN4{slash}C1INB{slash}RP28{slash}OCM3B{slash}RB4-Pad12)") (class "Default")
      (node (ref "PIC24FJ1024GA606") (pin "12") (pinfunction "PGED3/AN4/C1INB/RP28/OCM3B/RB4_12") (pintype "bidirectional"))
    )
    (net (code "167") (name "unconnected-(PIC24FJ1024GA606-PMD1{slash}RE1-Pad61)") (class "Default")
      (node (ref "PIC24FJ1024GA606") (pin "61") (pinfunction "PMD1/RE1_61") (pintype "bidirectional"))
    )
    (net (code "168") (name "unconnected-(PIC24FJ1024GA606-RP10{slash}SDA2{slash}PMA9{slash}RF4-Pad31)") (class "Default")
      (node (ref "PIC24FJ1024GA606") (pin "31") (pinfunction "RP10/SDA2/PMA9/RF4_31") (pintype "bidirectional"))
    )
    (net (code "169") (name "unconnected-(PIC24FJ1024GA606-RP17{slash}SCL2{slash}PMA8{slash}RF5-Pad32)") (class "Default")
      (node (ref "PIC24FJ1024GA606") (pin "32") (pinfunction "RP17/SCL2/PMA8/RF5_32") (pintype "bidirectional"))
    )
    (net (code "170") (name "unconnected-(PIC24FJ1024GA606-SCL1{slash}RG2-Pad37)") (class "Default")
      (node (ref "PIC24FJ1024GA606") (pin "37") (pinfunction "SCL1/RG2_37") (pintype "bidirectional"))
    )
    (net (code "171") (name "unconnected-(PIC24FJ1024GA606-SDA1{slash}RG3-Pad36)") (class "Default")
      (node (ref "PIC24FJ1024GA606") (pin "36") (pinfunction "SDA1/RG3_36") (pintype "bidirectional"))
    )
    (net (code "172") (name "unconnected-(PIC24FJ1024GA606-SOSCI{slash}C3IND{slash}RC13-Pad47)") (class "Default")
      (node (ref "PIC24FJ1024GA606") (pin "47") (pinfunction "SOSCI/C3IND/RC13_47") (pintype "bidirectional"))
    )
    (net (code "173") (name "unconnected-(PIC24FJ1024GA606-SOSCO{slash}C3INC{slash}RPI37{slash}PWRLCLK{slash}RC14-Pad48)") (class "Default")
      (node (ref "PIC24FJ1024GA606") (pin "48") (pinfunction "SOSCO/C3INC/RPI37/PWRLCLK/RC14_48") (pintype "bidirectional"))
    )
    (net (code "174") (name "unconnected-(PIC24FJ1024GA606-TCK{slash}AN12{slash}U6RX{slash}CTED2{slash}PMA11{slash}RB12-Pad27)") (class "Default")
      (node (ref "PIC24FJ1024GA606") (pin "27") (pinfunction "TCK/AN12/U6RX/CTED2/PMA11/RB12_27") (pintype "bidirectional"))
    )
    (net (code "175") (name "unconnected-(PIC24FJ1024GA606-TDI{slash}AN13{slash}CTED1{slash}PMA10{slash}RB13-Pad28)") (class "Default")
      (node (ref "PIC24FJ1024GA606") (pin "28") (pinfunction "TDI/AN13/CTED1/PMA10/RB13_28") (pintype "bidirectional"))
    )
    (net (code "176") (name "unconnected-(PIC24FJ1024GA606-TDO{slash}AN11{slash}REFI{slash}PMA12{slash}RB11-Pad24)") (class "Default")
      (node (ref "PIC24FJ1024GA606") (pin "24") (pinfunction "TDO/AN11/REFI/PMA12/RB11_24") (pintype "bidirectional"))
    )
    (net (code "177") (name "unconnected-(PIC24FJ1024GA606-TMS{slash}CVREF{slash}AN10{slash}PMA13{slash}RB10-Pad23)") (class "Default")
      (node (ref "PIC24FJ1024GA606") (pin "23") (pinfunction "TMS/CVREF/AN10/PMA13/RB10_23") (pintype "bidirectional"))
    )
    (net (code "178") (name "unconnected-(PIC24FJ1024GA606-U5CTS{slash}OC6{slash}RF0-Pad58)") (class "Default")
      (node (ref "PIC24FJ1024GA606") (pin "58") (pinfunction "U5CTS/OC6/RF0_58") (pintype "bidirectional"))
    )
    (net (code "179") (name "unconnected-(SPKR_OUT-Pad3)") (class "Default")
      (node (ref "SPKR_OUT") (pin "3") (pinfunction "3_3") (pintype "bidirectional"))
    )
    (net (code "180") (name "unconnected-(SPKR_OUT-Pad6)") (class "Default")
      (node (ref "SPKR_OUT") (pin "6") (pinfunction "6_6") (pintype "bidirectional"))
    )
    (net (code "181") (name "unconnected-(TH3122-RESET-Pad14)") (class "Default")
      (node (ref "TH3122") (pin "14") (pinfunction "RESET_14") (pintype "output"))
    )
    (net (code "182") (name "unconnected-(TH3122-SENSE-Pad15)") (class "Default")
      (node (ref "TH3122") (pin "15") (pinfunction "SENSE_15") (pintype "bidirectional"))
    )
    (net (code "183") (name "unconnected-(TH3122-SO-Pad8)") (class "Default")
      (node (ref "TH3122") (pin "8") (pinfunction "SO_8") (pintype "output"))
    )
    (net (code "184") (name "unconnected-(USB-ID-Pad4)") (class "Default")
      (node (ref "USB") (pin "4") (pinfunction "ID_4") (pintype "bidirectional"))
    )
    (net (code "185") (name "unconnected-(WM8804-CLKOUT-Pad9)") (class "Default")
      (node (ref "WM8804") (pin "9") (pinfunction "CLKOUT_9") (pintype "output"))
    )
    (net (code "186") (name "unconnected-(WM8804-DIN-Pad13)") (class "Default")
      (node (ref "WM8804") (pin "13") (pinfunction "DIN_13") (pintype "input"))
    )
    (net (code "187") (name "unconnected-(WM8804-SDOUT{slash}GPO2-Pad4)") (class "Default")
      (node (ref "WM8804") (pin "4") (pinfunction "SDOUT/GPO2_4") (pintype "output"))
    )
    (net (code "188") (name "unconnected-(XC6210-NC-Pad4)") (class "Default")
      (node (ref "XC6210") (pin "4") (pinfunction "NC_4") (pintype "no_connect"))
    )
    (net (code "189") (name "unconnected-(XC6702-NC-Pad4)") (class "Default")
      (node (ref "XC6702") (pin "4") (pinfunction "NC_4") (pintype "no_connect"))
    )
  )
)
